# E8-F.net
KiCad netlist of a schematic drawn in EAGLE
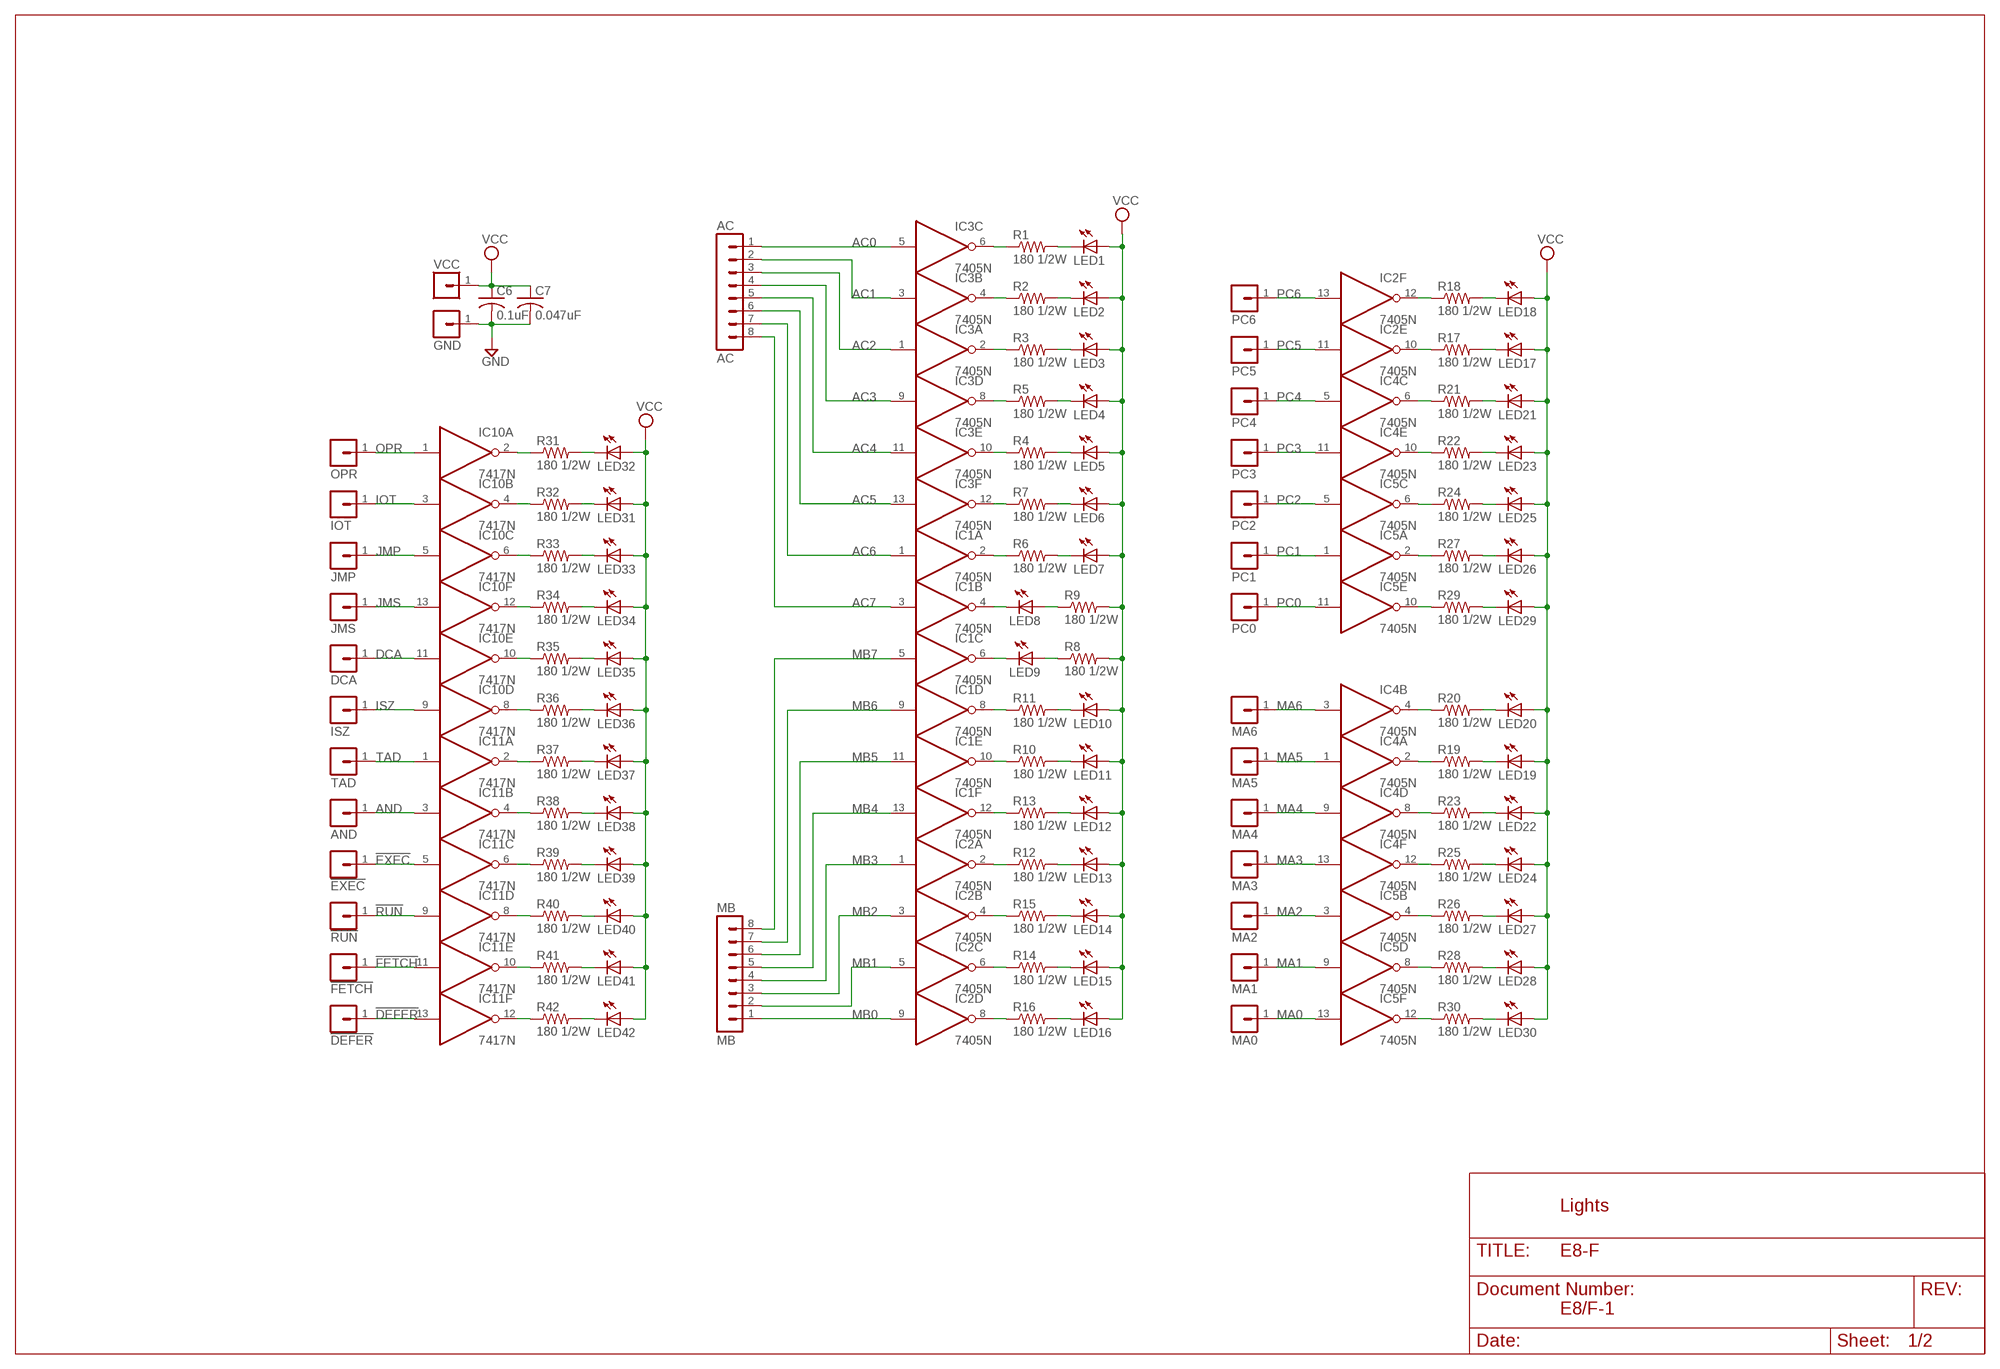
[diagram p0: schematic, sheet 1]
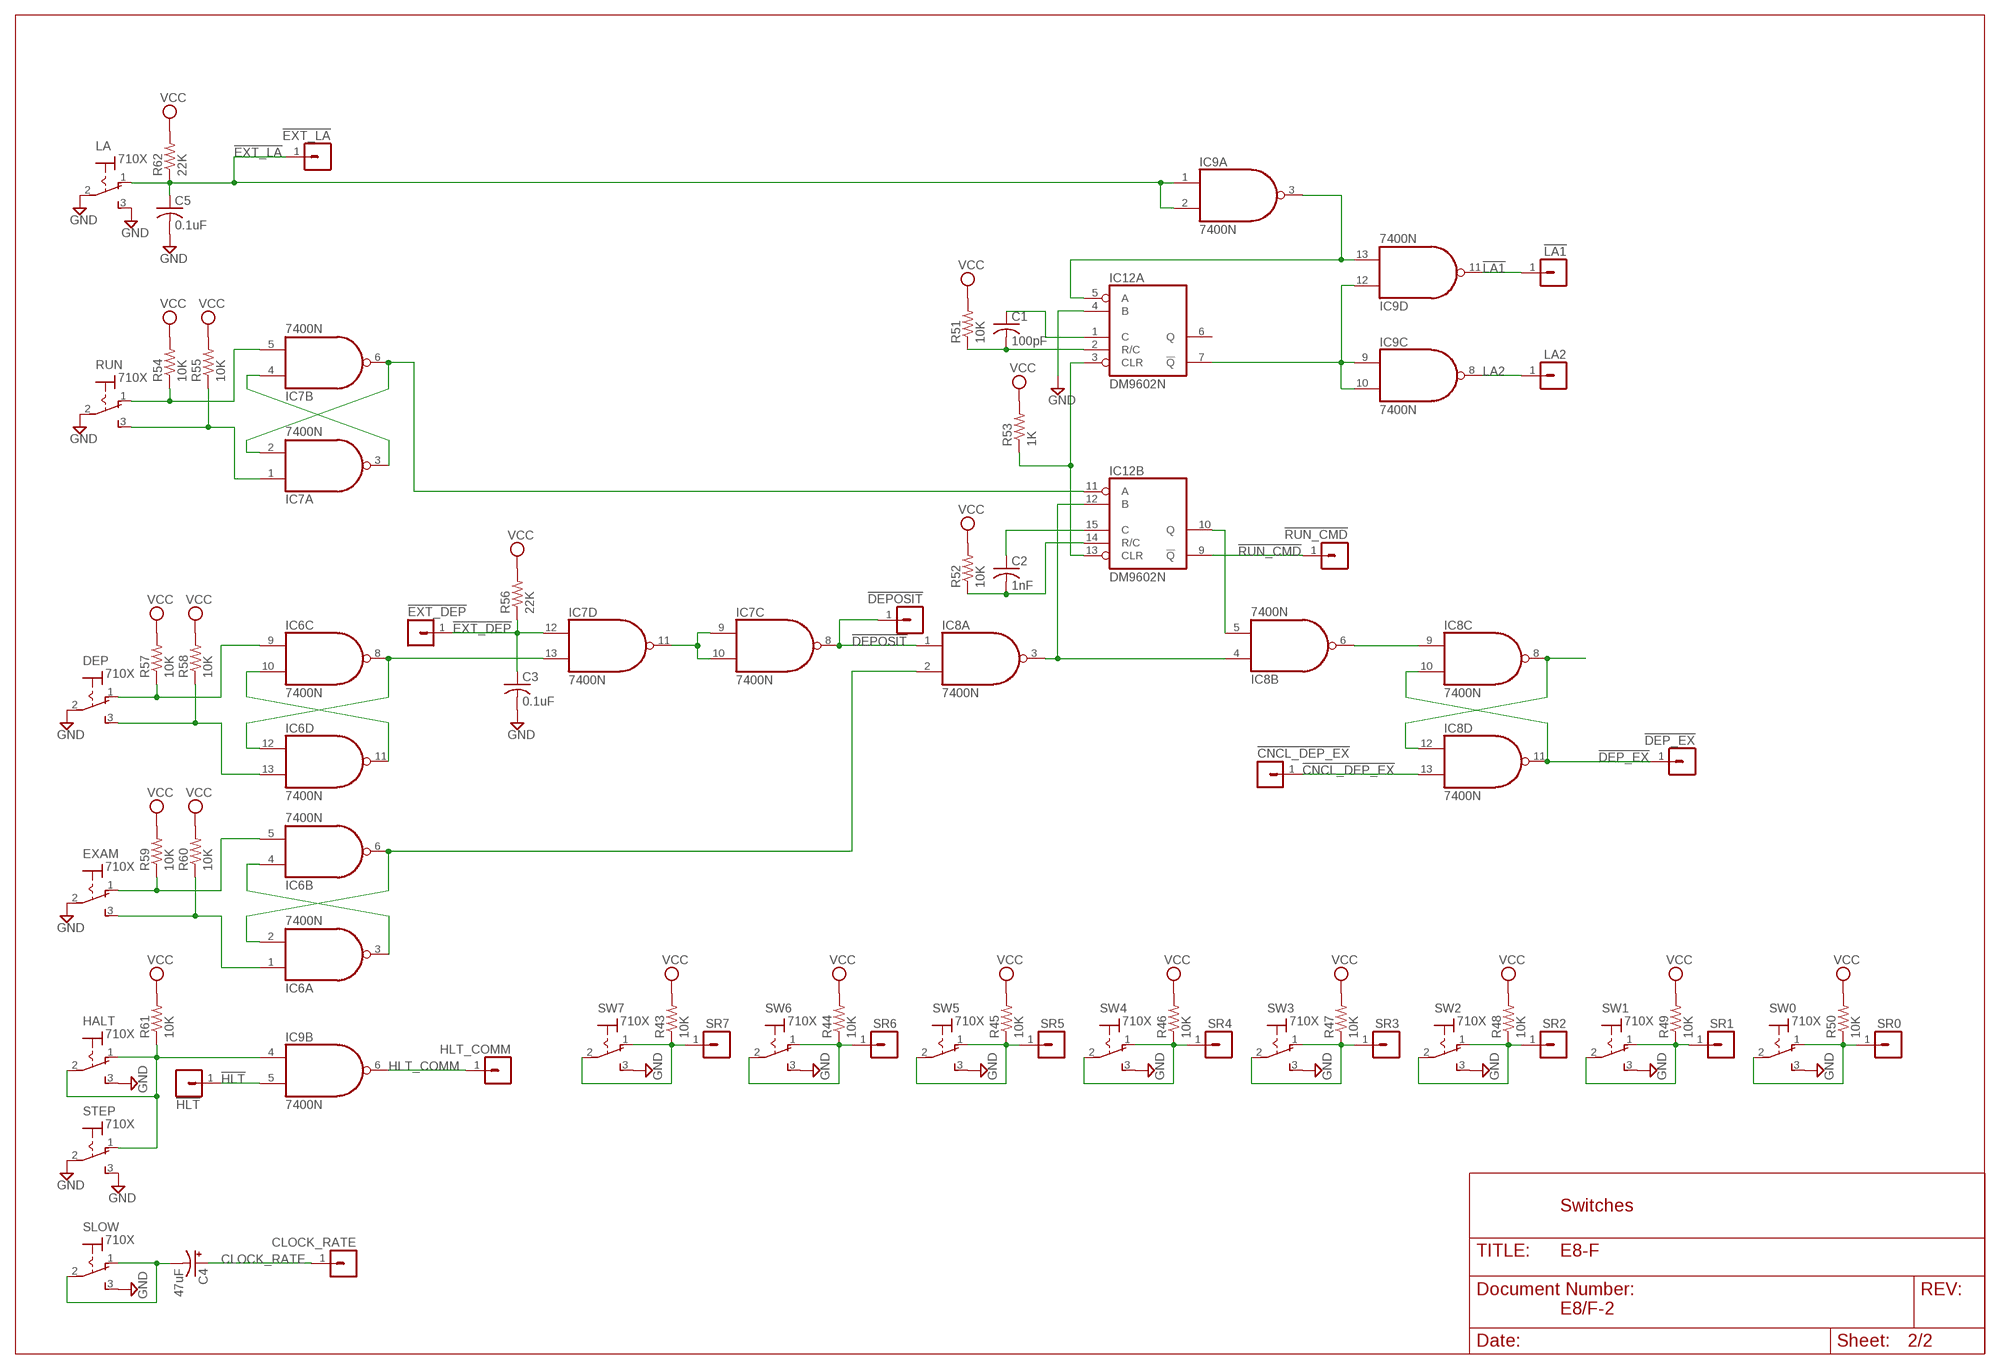
[diagram p1: schematic, sheet 2]

(export (version "E")
  (design (tool "Eeschema 10.0.6"))
  (components
    (comp (ref "!DEFER")
      (value "MA01-1")
      (footprint "eagle-import:MA01-1")
      (libsource (lib "eagle-import") (part "MA01-1"))
    )
    (comp (ref "!EXEC")
      (value "MA01-1")
      (footprint "eagle-import:MA01-1")
      (libsource (lib "eagle-import") (part "MA01-1"))
    )
    (comp (ref "!FETCH")
      (value "MA01-1")
      (footprint "eagle-import:MA01-1")
      (libsource (lib "eagle-import") (part "MA01-1"))
    )
    (comp (ref "!RUN")
      (value "MA01-1")
      (footprint "eagle-import:MA01-1")
      (libsource (lib "eagle-import") (part "MA01-1"))
    )
    (comp (ref "AC")
      (value "AC")
      (footprint "eagle-import:MA08-1")
      (libsource (lib "eagle-import") (part "MA08-1"))
    )
    (comp (ref "AND")
      (value "MA01-1")
      (footprint "eagle-import:MA01-1")
      (libsource (lib "eagle-import") (part "MA01-1"))
    )
    (comp (ref "C6")
      (value "0.1uF")
      (footprint "eagle-import:C075-032X103")
      (libsource (lib "eagle-import") (part "C-US075-032X103"))
    )
    (comp (ref "C7")
      (value "0.047uF")
      (footprint "eagle-import:C075-032X103")
      (libsource (lib "eagle-import") (part "C-US075-032X103"))
    )
    (comp (ref "DCA")
      (value "MA01-1")
      (footprint "eagle-import:MA01-1")
      (libsource (lib "eagle-import") (part "MA01-1"))
    )
    (comp (ref "GND")
      (value "MA01-1")
      (footprint "eagle-import:MA01-1")
      (libsource (lib "eagle-import") (part "MA01-1"))
    )
    (comp (ref "IC1")
      (value "7405N")
      (footprint "eagle-import:DIL14")
      (libsource (lib "eagle-import") (part "7405N"))
    )
    (comp (ref "IC2")
      (value "7405N")
      (footprint "eagle-import:DIL14")
      (libsource (lib "eagle-import") (part "7405N"))
    )
    (comp (ref "IC3")
      (value "7405N")
      (footprint "eagle-import:DIL14")
      (libsource (lib "eagle-import") (part "7405N"))
    )
    (comp (ref "IC4")
      (value "7405N")
      (footprint "eagle-import:DIL14")
      (libsource (lib "eagle-import") (part "7405N"))
    )
    (comp (ref "IC5")
      (value "7405N")
      (footprint "eagle-import:DIL14")
      (libsource (lib "eagle-import") (part "7405N"))
    )
    (comp (ref "IC10")
      (value "7417N")
      (footprint "eagle-import:DIL14")
      (libsource (lib "eagle-import") (part "7417N"))
    )
    (comp (ref "IC11")
      (value "7417N")
      (footprint "eagle-import:DIL14")
      (libsource (lib "eagle-import") (part "7417N"))
    )
    (comp (ref "IOT")
      (value "MA01-1")
      (footprint "eagle-import:MA01-1")
      (libsource (lib "eagle-import") (part "MA01-1"))
    )
    (comp (ref "ISZ")
      (value "MA01-1")
      (footprint "eagle-import:MA01-1")
      (libsource (lib "eagle-import") (part "MA01-1"))
    )
    (comp (ref "JMP")
      (value "MA01-1")
      (footprint "eagle-import:MA01-1")
      (libsource (lib "eagle-import") (part "MA01-1"))
    )
    (comp (ref "JMS")
      (value "MA01-1")
      (footprint "eagle-import:MA01-1")
      (libsource (lib "eagle-import") (part "MA01-1"))
    )
    (comp (ref "LED1")
      (value "LED5MM")
      (footprint "eagle-import:LED5MM")
      (libsource (lib "eagle-import") (part "LED5MM"))
    )
    (comp (ref "LED2")
      (value "LED5MM")
      (footprint "eagle-import:LED5MM")
      (libsource (lib "eagle-import") (part "LED5MM"))
    )
    (comp (ref "LED3")
      (value "LED5MM")
      (footprint "eagle-import:LED5MM")
      (libsource (lib "eagle-import") (part "LED5MM"))
    )
    (comp (ref "LED4")
      (value "LED5MM")
      (footprint "eagle-import:LED5MM")
      (libsource (lib "eagle-import") (part "LED5MM"))
    )
    (comp (ref "LED5")
      (value "LED5MM")
      (footprint "eagle-import:LED5MM")
      (libsource (lib "eagle-import") (part "LED5MM"))
    )
    (comp (ref "LED6")
      (value "LED5MM")
      (footprint "eagle-import:LED5MM")
      (libsource (lib "eagle-import") (part "LED5MM"))
    )
    (comp (ref "LED7")
      (value "LED5MM")
      (footprint "eagle-import:LED5MM")
      (libsource (lib "eagle-import") (part "LED5MM"))
    )
    (comp (ref "LED8")
      (value "LED5MM")
      (footprint "eagle-import:LED5MM")
      (libsource (lib "eagle-import") (part "LED5MM"))
    )
    (comp (ref "LED9")
      (value "LED5MM")
      (footprint "eagle-import:LED5MM")
      (libsource (lib "eagle-import") (part "LED5MM"))
    )
    (comp (ref "LED10")
      (value "LED5MM")
      (footprint "eagle-import:LED5MM")
      (libsource (lib "eagle-import") (part "LED5MM"))
    )
    (comp (ref "LED11")
      (value "LED5MM")
      (footprint "eagle-import:LED5MM")
      (libsource (lib "eagle-import") (part "LED5MM"))
    )
    (comp (ref "LED12")
      (value "LED5MM")
      (footprint "eagle-import:LED5MM")
      (libsource (lib "eagle-import") (part "LED5MM"))
    )
    (comp (ref "LED13")
      (value "LED5MM")
      (footprint "eagle-import:LED5MM")
      (libsource (lib "eagle-import") (part "LED5MM"))
    )
    (comp (ref "LED14")
      (value "LED5MM")
      (footprint "eagle-import:LED5MM")
      (libsource (lib "eagle-import") (part "LED5MM"))
    )
    (comp (ref "LED15")
      (value "LED5MM")
      (footprint "eagle-import:LED5MM")
      (libsource (lib "eagle-import") (part "LED5MM"))
    )
    (comp (ref "LED16")
      (value "LED5MM")
      (footprint "eagle-import:LED5MM")
      (libsource (lib "eagle-import") (part "LED5MM"))
    )
    (comp (ref "LED17")
      (value "LED5MM")
      (footprint "eagle-import:LED5MM")
      (libsource (lib "eagle-import") (part "LED5MM"))
    )
    (comp (ref "LED18")
      (value "LED5MM")
      (footprint "eagle-import:LED5MM")
      (libsource (lib "eagle-import") (part "LED5MM"))
    )
    (comp (ref "LED19")
      (value "LED5MM")
      (footprint "eagle-import:LED5MM")
      (libsource (lib "eagle-import") (part "LED5MM"))
    )
    (comp (ref "LED20")
      (value "LED5MM")
      (footprint "eagle-import:LED5MM")
      (libsource (lib "eagle-import") (part "LED5MM"))
    )
    (comp (ref "LED21")
      (value "LED5MM")
      (footprint "eagle-import:LED5MM")
      (libsource (lib "eagle-import") (part "LED5MM"))
    )
    (comp (ref "LED22")
      (value "LED5MM")
      (footprint "eagle-import:LED5MM")
      (libsource (lib "eagle-import") (part "LED5MM"))
    )
    (comp (ref "LED23")
      (value "LED5MM")
      (footprint "eagle-import:LED5MM")
      (libsource (lib "eagle-import") (part "LED5MM"))
    )
    (comp (ref "LED24")
      (value "LED5MM")
      (footprint "eagle-import:LED5MM")
      (libsource (lib "eagle-import") (part "LED5MM"))
    )
    (comp (ref "LED25")
      (value "LED5MM")
      (footprint "eagle-import:LED5MM")
      (libsource (lib "eagle-import") (part "LED5MM"))
    )
    (comp (ref "LED26")
      (value "LED5MM")
      (footprint "eagle-import:LED5MM")
      (libsource (lib "eagle-import") (part "LED5MM"))
    )
    (comp (ref "LED27")
      (value "LED5MM")
      (footprint "eagle-import:LED5MM")
      (libsource (lib "eagle-import") (part "LED5MM"))
    )
    (comp (ref "LED28")
      (value "LED5MM")
      (footprint "eagle-import:LED5MM")
      (libsource (lib "eagle-import") (part "LED5MM"))
    )
    (comp (ref "LED29")
      (value "LED5MM")
      (footprint "eagle-import:LED5MM")
      (libsource (lib "eagle-import") (part "LED5MM"))
    )
    (comp (ref "LED30")
      (value "LED5MM")
      (footprint "eagle-import:LED5MM")
      (libsource (lib "eagle-import") (part "LED5MM"))
    )
    (comp (ref "LED31")
      (value "LED5MM")
      (footprint "eagle-import:LED5MM")
      (libsource (lib "eagle-import") (part "LED5MM"))
    )
    (comp (ref "LED32")
      (value "LED5MM")
      (footprint "eagle-import:LED5MM")
      (libsource (lib "eagle-import") (part "LED5MM"))
    )
    (comp (ref "LED33")
      (value "LED5MM")
      (footprint "eagle-import:LED5MM")
      (libsource (lib "eagle-import") (part "LED5MM"))
    )
    (comp (ref "LED34")
      (value "LED5MM")
      (footprint "eagle-import:LED5MM")
      (libsource (lib "eagle-import") (part "LED5MM"))
    )
    (comp (ref "LED35")
      (value "LED5MM")
      (footprint "eagle-import:LED5MM")
      (libsource (lib "eagle-import") (part "LED5MM"))
    )
    (comp (ref "LED36")
      (value "LED5MM")
      (footprint "eagle-import:LED5MM")
      (libsource (lib "eagle-import") (part "LED5MM"))
    )
    (comp (ref "LED37")
      (value "LED5MM")
      (footprint "eagle-import:LED5MM")
      (libsource (lib "eagle-import") (part "LED5MM"))
    )
    (comp (ref "LED38")
      (value "LED5MM")
      (footprint "eagle-import:LED5MM")
      (libsource (lib "eagle-import") (part "LED5MM"))
    )
    (comp (ref "LED39")
      (value "LED5MM")
      (footprint "eagle-import:LED5MM")
      (libsource (lib "eagle-import") (part "LED5MM"))
    )
    (comp (ref "LED40")
      (value "LED5MM")
      (footprint "eagle-import:LED5MM")
      (libsource (lib "eagle-import") (part "LED5MM"))
    )
    (comp (ref "LED41")
      (value "LED5MM")
      (footprint "eagle-import:LED5MM")
      (libsource (lib "eagle-import") (part "LED5MM"))
    )
    (comp (ref "LED42")
      (value "LED5MM")
      (footprint "eagle-import:LED5MM")
      (libsource (lib "eagle-import") (part "LED5MM"))
    )
    (comp (ref "MA0")
      (value "MA01-1")
      (footprint "eagle-import:MA01-1")
      (libsource (lib "eagle-import") (part "MA01-1"))
    )
    (comp (ref "MA1")
      (value "MA01-1")
      (footprint "eagle-import:MA01-1")
      (libsource (lib "eagle-import") (part "MA01-1"))
    )
    (comp (ref "MA2")
      (value "MA01-1")
      (footprint "eagle-import:MA01-1")
      (libsource (lib "eagle-import") (part "MA01-1"))
    )
    (comp (ref "MA3")
      (value "MA01-1")
      (footprint "eagle-import:MA01-1")
      (libsource (lib "eagle-import") (part "MA01-1"))
    )
    (comp (ref "MA4")
      (value "MA01-1")
      (footprint "eagle-import:MA01-1")
      (libsource (lib "eagle-import") (part "MA01-1"))
    )
    (comp (ref "MA5")
      (value "MA01-1")
      (footprint "eagle-import:MA01-1")
      (libsource (lib "eagle-import") (part "MA01-1"))
    )
    (comp (ref "MA6")
      (value "MA01-1")
      (footprint "eagle-import:MA01-1")
      (libsource (lib "eagle-import") (part "MA01-1"))
    )
    (comp (ref "MB")
      (value "MB")
      (footprint "eagle-import:MA08-1")
      (libsource (lib "eagle-import") (part "MA08-1"))
    )
    (comp (ref "OPR")
      (value "MA01-1")
      (footprint "eagle-import:MA01-1")
      (libsource (lib "eagle-import") (part "MA01-1"))
    )
    (comp (ref "PC0")
      (value "MA01-1")
      (footprint "eagle-import:MA01-1")
      (libsource (lib "eagle-import") (part "MA01-1"))
    )
    (comp (ref "PC1")
      (value "MA01-1")
      (footprint "eagle-import:MA01-1")
      (libsource (lib "eagle-import") (part "MA01-1"))
    )
    (comp (ref "PC2")
      (value "MA01-1")
      (footprint "eagle-import:MA01-1")
      (libsource (lib "eagle-import") (part "MA01-1"))
    )
    (comp (ref "PC3")
      (value "MA01-1")
      (footprint "eagle-import:MA01-1")
      (libsource (lib "eagle-import") (part "MA01-1"))
    )
    (comp (ref "PC4")
      (value "MA01-1")
      (footprint "eagle-import:MA01-1")
      (libsource (lib "eagle-import") (part "MA01-1"))
    )
    (comp (ref "PC5")
      (value "MA01-1")
      (footprint "eagle-import:MA01-1")
      (libsource (lib "eagle-import") (part "MA01-1"))
    )
    (comp (ref "PC6")
      (value "MA01-1")
      (footprint "eagle-import:MA01-1")
      (libsource (lib "eagle-import") (part "MA01-1"))
    )
    (comp (ref "R1")
      (value "180 1/2W")
      (footprint "eagle-import:0309_.45")
      (libsource (lib "eagle-import") (part "R-US_0309/.45"))
    )
    (comp (ref "R2")
      (value "180 1/2W")
      (footprint "eagle-import:0309_.45")
      (libsource (lib "eagle-import") (part "R-US_0309/.45"))
    )
    (comp (ref "R3")
      (value "180 1/2W")
      (footprint "eagle-import:0309_.45")
      (libsource (lib "eagle-import") (part "R-US_0309/.45"))
    )
    (comp (ref "R4")
      (value "180 1/2W")
      (footprint "eagle-import:0309_12")
      (libsource (lib "eagle-import") (part "rcl_R-US_0309/12"))
    )
    (comp (ref "R5")
      (value "180 1/2W")
      (footprint "eagle-import:0309_.45")
      (libsource (lib "eagle-import") (part "R-US_0309/.45"))
    )
    (comp (ref "R6")
      (value "180 1/2W")
      (footprint "eagle-import:0309_12")
      (libsource (lib "eagle-import") (part "rcl_R-US_0309/12"))
    )
    (comp (ref "R7")
      (value "180 1/2W")
      (footprint "eagle-import:0309_.45")
      (libsource (lib "eagle-import") (part "R-US_0309/.45"))
    )
    (comp (ref "R8")
      (value "180 1/2W")
      (footprint "eagle-import:0309_12")
      (libsource (lib "eagle-import") (part "rcl_R-US_0309/12"))
    )
    (comp (ref "R9")
      (value "180 1/2W")
      (footprint "eagle-import:0309_12")
      (libsource (lib "eagle-import") (part "rcl_R-US_0309/12"))
    )
    (comp (ref "R10")
      (value "180 1/2W")
      (footprint "eagle-import:0309_.45")
      (libsource (lib "eagle-import") (part "R-US_0309/.45"))
    )
    (comp (ref "R11")
      (value "180 1/2W")
      (footprint "eagle-import:0309_11")
      (libsource (lib "eagle-import") (part "R-US_0309/11"))
    )
    (comp (ref "R12")
      (value "180 1/2W")
      (footprint "eagle-import:0309_12")
      (libsource (lib "eagle-import") (part "rcl_R-US_0309/12"))
    )
    (comp (ref "R13")
      (value "180 1/2W")
      (footprint "eagle-import:0309_.45")
      (libsource (lib "eagle-import") (part "R-US_0309/.45"))
    )
    (comp (ref "R14")
      (value "180 1/2W")
      (footprint "eagle-import:0309_.45")
      (libsource (lib "eagle-import") (part "R-US_0309/.45"))
    )
    (comp (ref "R15")
      (value "180 1/2W")
      (footprint "eagle-import:0309_12")
      (libsource (lib "eagle-import") (part "rcl_R-US_0309/12"))
    )
    (comp (ref "R16")
      (value "180 1/2W")
      (footprint "eagle-import:0309_12")
      (libsource (lib "eagle-import") (part "rcl_R-US_0309/12"))
    )
    (comp (ref "R17")
      (value "180 1/2W")
      (footprint "eagle-import:0309_12")
      (libsource (lib "eagle-import") (part "rcl_R-US_0309/12"))
    )
    (comp (ref "R18")
      (value "180 1/2W")
      (footprint "eagle-import:0309_12")
      (libsource (lib "eagle-import") (part "rcl_R-US_0309/12"))
    )
    (comp (ref "R19")
      (value "180 1/2W")
      (footprint "eagle-import:0309_12")
      (libsource (lib "eagle-import") (part "R-US_0309/12"))
    )
    (comp (ref "R20")
      (value "180 1/2W")
      (footprint "eagle-import:0309_15")
      (libsource (lib "eagle-import") (part "R-US_0309/15"))
    )
    (comp (ref "R21")
      (value "180 1/2W")
      (footprint "eagle-import:0309_.45")
      (libsource (lib "eagle-import") (part "R-US_0309/.45"))
    )
    (comp (ref "R22")
      (value "180 1/2W")
      (footprint "eagle-import:0309_10")
      (libsource (lib "eagle-import") (part "R-US_0309/10"))
    )
    (comp (ref "R23")
      (value "180 1/2W")
      (footprint "eagle-import:0309_10")
      (libsource (lib "eagle-import") (part "rcl_R-US_0309/10"))
    )
    (comp (ref "R24")
      (value "180 1/2W")
      (footprint "eagle-import:0309_12")
      (libsource (lib "eagle-import") (part "rcl_R-US_0309/12"))
    )
    (comp (ref "R25")
      (value "180 1/2W")
      (footprint "eagle-import:0309_10")
      (libsource (lib "eagle-import") (part "rcl_R-US_0309/10"))
    )
    (comp (ref "R26")
      (value "180 1/2W")
      (footprint "eagle-import:0309_10")
      (libsource (lib "eagle-import") (part "R-US_0309/10"))
    )
    (comp (ref "R27")
      (value "180 1/2W")
      (footprint "eagle-import:0309_15")
      (libsource (lib "eagle-import") (part "R-US_0309/15"))
    )
    (comp (ref "R28")
      (value "180 1/2W")
      (footprint "eagle-import:0309_.45")
      (libsource (lib "eagle-import") (part "R-US_0309/.45"))
    )
    (comp (ref "R29")
      (value "180 1/2W")
      (footprint "eagle-import:0309_.45")
      (libsource (lib "eagle-import") (part "R-US_0309/.45"))
    )
    (comp (ref "R30")
      (value "180 1/2W")
      (footprint "eagle-import:0309_.45")
      (libsource (lib "eagle-import") (part "R-US_0309/.45"))
    )
    (comp (ref "R31")
      (value "180 1/2W")
      (footprint "eagle-import:0309_8")
      (libsource (lib "eagle-import") (part "R-US_0309/8"))
    )
    (comp (ref "R32")
      (value "180 1/2W")
      (footprint "eagle-import:0309_8")
      (libsource (lib "eagle-import") (part "R-US_0309/8"))
    )
    (comp (ref "R33")
      (value "180 1/2W")
      (footprint "eagle-import:0309_8")
      (libsource (lib "eagle-import") (part "R-US_0309/8"))
    )
    (comp (ref "R34")
      (value "180 1/2W")
      (footprint "eagle-import:0309_8")
      (libsource (lib "eagle-import") (part "R-US_0309/8"))
    )
    (comp (ref "R35")
      (value "180 1/2W")
      (footprint "eagle-import:0309_8")
      (libsource (lib "eagle-import") (part "R-US_0309/8"))
    )
    (comp (ref "R36")
      (value "180 1/2W")
      (footprint "eagle-import:0309_8")
      (libsource (lib "eagle-import") (part "R-US_0309/8"))
    )
    (comp (ref "R37")
      (value "180 1/2W")
      (footprint "eagle-import:0309_8")
      (libsource (lib "eagle-import") (part "R-US_0309/8"))
    )
    (comp (ref "R38")
      (value "180 1/2W")
      (footprint "eagle-import:0309_8")
      (libsource (lib "eagle-import") (part "R-US_0309/8"))
    )
    (comp (ref "R39")
      (value "180 1/2W")
      (footprint "eagle-import:0309_10")
      (libsource (lib "eagle-import") (part "R-US_0309/10"))
    )
    (comp (ref "R40")
      (value "180 1/2W")
      (footprint "eagle-import:0309_10")
      (libsource (lib "eagle-import") (part "R-US_0309/10"))
    )
    (comp (ref "R41")
      (value "180 1/2W")
      (footprint "eagle-import:0309_10")
      (libsource (lib "eagle-import") (part "R-US_0309/10"))
    )
    (comp (ref "R42")
      (value "180 1/2W")
      (footprint "eagle-import:0309_10")
      (libsource (lib "eagle-import") (part "R-US_0309/10"))
    )
    (comp (ref "TAD")
      (value "MA01-1")
      (footprint "eagle-import:MA01-1")
      (libsource (lib "eagle-import") (part "MA01-1"))
    )
    (comp (ref "VCC")
      (value "MA01-1")
      (footprint "eagle-import:MA01-1")
      (libsource (lib "eagle-import") (part "MA01-1"))
    )
    (comp (ref "!CNCL_DEP_EX")
      (value "MA01-1")
      (footprint "eagle-import:MA01-1")
      (libsource (lib "eagle-import") (part "MA01-1"))
    )
    (comp (ref "!DEPOSIT")
      (value "MA01-1")
      (footprint "eagle-import:MA01-1")
      (libsource (lib "eagle-import") (part "MA01-1"))
    )
    (comp (ref "!DEP_EX")
      (value "MA01-1")
      (footprint "eagle-import:MA01-1")
      (libsource (lib "eagle-import") (part "MA01-1"))
    )
    (comp (ref "!EXT_DEP")
      (value "MA01-1")
      (footprint "eagle-import:MA01-1")
      (libsource (lib "eagle-import") (part "MA01-1"))
    )
    (comp (ref "!EXT_LA")
      (value "MA01-1")
      (footprint "eagle-import:MA01-1")
      (libsource (lib "eagle-import") (part "MA01-1"))
    )
    (comp (ref "!HLT")
      (value "MA01-1")
      (footprint "eagle-import:MA01-1")
      (libsource (lib "eagle-import") (part "MA01-1"))
    )
    (comp (ref "!LA1")
      (value "MA01-1")
      (footprint "eagle-import:MA01-1")
      (libsource (lib "eagle-import") (part "MA01-1"))
    )
    (comp (ref "!RUN_CMD")
      (value "MA01-1")
      (footprint "eagle-import:MA01-1")
      (libsource (lib "eagle-import") (part "MA01-1"))
    )
    (comp (ref "C1")
      (value "100pF")
      (footprint "eagle-import:C075-032X103")
      (libsource (lib "eagle-import") (part "C-US075-032X103"))
    )
    (comp (ref "C2")
      (value "1nF")
      (footprint "eagle-import:C075-032X103")
      (libsource (lib "eagle-import") (part "C-US075-032X103"))
    )
    (comp (ref "C3")
      (value "0.1uF")
      (footprint "eagle-import:C063-025X075")
      (libsource (lib "eagle-import") (part "C-US"))
    )
    (comp (ref "C4")
      (value "47uF")
      (footprint "eagle-import:B45181C")
      (libsource (lib "eagle-import") (part "CPOL-USB45181C"))
    )
    (comp (ref "C5")
      (value "0.1uF")
      (footprint "eagle-import:C075-032X103")
      (libsource (lib "eagle-import") (part "C-US075-032X103"))
    )
    (comp (ref "CLOCK_RATE")
      (value "MA01-1")
      (footprint "eagle-import:MA01-1")
      (libsource (lib "eagle-import") (part "MA01-1"))
    )
    (comp (ref "DEP")
      (value "710X")
      (footprint "eagle-import:7109")
      (libsource (lib "eagle-import") (part "710X"))
    )
    (comp (ref "EXAM")
      (value "710X")
      (footprint "eagle-import:7109")
      (libsource (lib "eagle-import") (part "710X"))
    )
    (comp (ref "HALT")
      (value "710X")
      (footprint "eagle-import:7109")
      (libsource (lib "eagle-import") (part "710X"))
    )
    (comp (ref "HLT_COMM")
      (value "MA01-1")
      (footprint "eagle-import:MA01-1")
      (libsource (lib "eagle-import") (part "MA01-1"))
    )
    (comp (ref "IC6")
      (value "7400N")
      (footprint "eagle-import:DIL14")
      (libsource (lib "eagle-import") (part "7400N"))
    )
    (comp (ref "IC7")
      (value "7400N")
      (footprint "eagle-import:DIL14")
      (libsource (lib "eagle-import") (part "7400N"))
    )
    (comp (ref "IC8")
      (value "7400N")
      (footprint "eagle-import:DIL14")
      (libsource (lib "eagle-import") (part "7400N"))
    )
    (comp (ref "IC9")
      (value "7400N")
      (footprint "eagle-import:DIL14")
      (libsource (lib "eagle-import") (part "7400N"))
    )
    (comp (ref "IC12")
      (value "DM9602N")
      (footprint "eagle-import:DIL16")
      (libsource (lib "eagle-import") (part "DM9602N"))
    )
    (comp (ref "LA")
      (value "710X")
      (footprint "eagle-import:7109")
      (libsource (lib "eagle-import") (part "710X"))
    )
    (comp (ref "LA2")
      (value "MA01-1")
      (footprint "eagle-import:MA01-1")
      (libsource (lib "eagle-import") (part "MA01-1"))
    )
    (comp (ref "R43")
      (value "10K")
      (footprint "eagle-import:0207_12")
      (libsource (lib "eagle-import") (part "rcl_R-US_0207/12"))
    )
    (comp (ref "R44")
      (value "10K")
      (footprint "eagle-import:0207_12")
      (libsource (lib "eagle-import") (part "rcl_R-US_0207/12"))
    )
    (comp (ref "R45")
      (value "10K")
      (footprint "eagle-import:0207_12")
      (libsource (lib "eagle-import") (part "rcl_R-US_0207/12"))
    )
    (comp (ref "R46")
      (value "10K")
      (footprint "eagle-import:0207_12")
      (libsource (lib "eagle-import") (part "rcl_R-US_0207/12"))
    )
    (comp (ref "R47")
      (value "10K")
      (footprint "eagle-import:0207_12")
      (libsource (lib "eagle-import") (part "rcl_R-US_0207/12"))
    )
    (comp (ref "R48")
      (value "10K")
      (footprint "eagle-import:0207_12")
      (libsource (lib "eagle-import") (part "rcl_R-US_0207/12"))
    )
    (comp (ref "R49")
      (value "10K")
      (footprint "eagle-import:0207_12")
      (libsource (lib "eagle-import") (part "rcl_R-US_0207/12"))
    )
    (comp (ref "R50")
      (value "10K")
      (footprint "eagle-import:0207_12")
      (libsource (lib "eagle-import") (part "rcl_R-US_0207/12"))
    )
    (comp (ref "R51")
      (value "10K")
      (footprint "eagle-import:0207_10")
      (libsource (lib "eagle-import") (part "rcl_R-US_0207/10"))
    )
    (comp (ref "R52")
      (value "10K")
      (footprint "eagle-import:0207_15")
      (libsource (lib "eagle-import") (part "rcl_R-US_0207/15"))
    )
    (comp (ref "R53")
      (value "1K")
      (footprint "eagle-import:0204_6")
      (libsource (lib "eagle-import") (part "R-US_0204/6"))
    )
    (comp (ref "R54")
      (value "10K")
      (footprint "eagle-import:0207_13")
      (libsource (lib "eagle-import") (part "R-US_0207/13"))
    )
    (comp (ref "R55")
      (value "10K")
      (footprint "eagle-import:0207_13")
      (libsource (lib "eagle-import") (part "R-US_0207/13"))
    )
    (comp (ref "R56")
      (value "22K")
      (footprint "eagle-import:0207_10")
      (libsource (lib "eagle-import") (part "R-US_0207/10"))
    )
    (comp (ref "R57")
      (value "10K")
      (footprint "eagle-import:0207_13")
      (libsource (lib "eagle-import") (part "R-US_0207/13"))
    )
    (comp (ref "R58")
      (value "10K")
      (footprint "eagle-import:0207_13")
      (libsource (lib "eagle-import") (part "R-US_0207/13"))
    )
    (comp (ref "R59")
      (value "10K")
      (footprint "eagle-import:0207_13")
      (libsource (lib "eagle-import") (part "R-US_0207/13"))
    )
    (comp (ref "R60")
      (value "10K")
      (footprint "eagle-import:0207_13")
      (libsource (lib "eagle-import") (part "R-US_0207/13"))
    )
    (comp (ref "R61")
      (value "10K")
      (footprint "eagle-import:0207_22")
      (libsource (lib "eagle-import") (part "R-US_0207/22"))
    )
    (comp (ref "R62")
      (value "22K")
      (footprint "eagle-import:0207_13")
      (libsource (lib "eagle-import") (part "R-US_0207/13"))
    )
    (comp (ref "RUN")
      (value "710X")
      (footprint "eagle-import:7109")
      (libsource (lib "eagle-import") (part "710X"))
    )
    (comp (ref "SLOW")
      (value "710X")
      (footprint "eagle-import:7109")
      (libsource (lib "eagle-import") (part "710X"))
    )
    (comp (ref "SR0")
      (value "MA01-1")
      (footprint "eagle-import:MA01-1")
      (libsource (lib "eagle-import") (part "MA01-1"))
    )
    (comp (ref "SR1")
      (value "MA01-1")
      (footprint "eagle-import:MA01-1")
      (libsource (lib "eagle-import") (part "MA01-1"))
    )
    (comp (ref "SR2")
      (value "MA01-1")
      (footprint "eagle-import:MA01-1")
      (libsource (lib "eagle-import") (part "MA01-1"))
    )
    (comp (ref "SR3")
      (value "MA01-1")
      (footprint "eagle-import:MA01-1")
      (libsource (lib "eagle-import") (part "MA01-1"))
    )
    (comp (ref "SR4")
      (value "MA01-1")
      (footprint "eagle-import:MA01-1")
      (libsource (lib "eagle-import") (part "MA01-1"))
    )
    (comp (ref "SR5")
      (value "MA01-1")
      (footprint "eagle-import:MA01-1")
      (libsource (lib "eagle-import") (part "MA01-1"))
    )
    (comp (ref "SR6")
      (value "MA01-1")
      (footprint "eagle-import:MA01-1")
      (libsource (lib "eagle-import") (part "MA01-1"))
    )
    (comp (ref "SR7")
      (value "MA01-1")
      (footprint "eagle-import:MA01-1")
      (libsource (lib "eagle-import") (part "MA01-1"))
    )
    (comp (ref "STEP")
      (value "710X")
      (footprint "eagle-import:7109")
      (libsource (lib "eagle-import") (part "710X"))
    )
    (comp (ref "SW0")
      (value "710X")
      (footprint "eagle-import:7109")
      (libsource (lib "eagle-import") (part "710X"))
    )
    (comp (ref "SW1")
      (value "710X")
      (footprint "eagle-import:7109")
      (libsource (lib "eagle-import") (part "710X"))
    )
    (comp (ref "SW2")
      (value "710X")
      (footprint "eagle-import:7109")
      (libsource (lib "eagle-import") (part "710X"))
    )
    (comp (ref "SW3")
      (value "710X")
      (footprint "eagle-import:7109")
      (libsource (lib "eagle-import") (part "710X"))
    )
    (comp (ref "SW4")
      (value "710X")
      (footprint "eagle-import:7109")
      (libsource (lib "eagle-import") (part "710X"))
    )
    (comp (ref "SW5")
      (value "710X")
      (footprint "eagle-import:7109")
      (libsource (lib "eagle-import") (part "710X"))
    )
    (comp (ref "SW6")
      (value "710X")
      (footprint "eagle-import:7109")
      (libsource (lib "eagle-import") (part "710X"))
    )
    (comp (ref "SW7")
      (value "710X")
      (footprint "eagle-import:7109")
      (libsource (lib "eagle-import") (part "710X"))
    )
  )
  (nets
    (net (code "1") (name "AC0") (class "Default")
      (node (ref "AC") (pin "1") (pinfunction "1_1") (pintype "passive"))
      (node (ref "IC3") (pin "5") (pinfunction "I_5") (pintype "input"))
    )
    (net (code "2") (name "AC1") (class "Default")
      (node (ref "AC") (pin "2") (pinfunction "2_2") (pintype "passive"))
      (node (ref "IC3") (pin "3") (pinfunction "I_3") (pintype "input"))
    )
    (net (code "3") (name "AC2") (class "Default")
      (node (ref "AC") (pin "3") (pinfunction "3_3") (pintype "passive"))
      (node (ref "IC3") (pin "1") (pinfunction "I_1") (pintype "input"))
    )
    (net (code "4") (name "AC3") (class "Default")
      (node (ref "AC") (pin "4") (pinfunction "4_4") (pintype "passive"))
      (node (ref "IC3") (pin "9") (pinfunction "I_9") (pintype "input"))
    )
    (net (code "5") (name "AC4") (class "Default")
      (node (ref "AC") (pin "5") (pinfunction "5_5") (pintype "passive"))
      (node (ref "IC3") (pin "11") (pinfunction "I_11") (pintype "input"))
    )
    (net (code "6") (name "AC5") (class "Default")
      (node (ref "AC") (pin "6") (pinfunction "6_6") (pintype "passive"))
      (node (ref "IC3") (pin "13") (pinfunction "I_13") (pintype "input"))
    )
    (net (code "7") (name "AC6") (class "Default")
      (node (ref "AC") (pin "7") (pinfunction "7_7") (pintype "passive"))
      (node (ref "IC1") (pin "1") (pinfunction "I_1") (pintype "input"))
    )
    (net (code "8") (name "AC7") (class "Default")
      (node (ref "AC") (pin "8") (pinfunction "8_8") (pintype "passive"))
      (node (ref "IC1") (pin "3") (pinfunction "I_3") (pintype "input"))
    )
    (net (code "9") (name "AND") (class "Default")
      (node (ref "AND") (pin "1") (pinfunction "1_1") (pintype "passive"))
      (node (ref "IC11") (pin "3") (pinfunction "I_3") (pintype "input"))
    )
    (net (code "10") (name "CLOCK_RATE") (class "Default")
      (node (ref "C4") (pin "+") (pinfunction "+_+") (pintype "passive"))
      (node (ref "CLOCK_RATE") (pin "1") (pinfunction "1_1") (pintype "passive"))
    )
    (net (code "11") (name "DCA") (class "Default")
      (node (ref "DCA") (pin "1") (pinfunction "1_1") (pintype "passive"))
      (node (ref "IC10") (pin "11") (pinfunction "I_11") (pintype "input"))
    )
    (net (code "12") (name "GND") (class "Default")
      (node (ref "C3") (pin "2") (pinfunction "2_2") (pintype "passive"))
      (node (ref "C5") (pin "2") (pinfunction "2_2") (pintype "passive"))
      (node (ref "C6") (pin "2") (pinfunction "2_2") (pintype "passive"))
      (node (ref "C7") (pin "2") (pinfunction "2_2") (pintype "passive"))
      (node (ref "DEP") (pin "2") (pinfunction "P_2") (pintype "passive"))
      (node (ref "EXAM") (pin "2") (pinfunction "P_2") (pintype "passive"))
      (node (ref "GND") (pin "1") (pinfunction "1_1") (pintype "passive"))
      (node (ref "HALT") (pin "3") (pinfunction "S_3") (pintype "passive"))
      (node (ref "IC12") (pin "4") (pinfunction "B_4") (pintype "input"))
      (node (ref "LA") (pin "2") (pinfunction "P_2") (pintype "passive"))
      (node (ref "LA") (pin "3") (pinfunction "S_3") (pintype "passive"))
      (node (ref "RUN") (pin "2") (pinfunction "P_2") (pintype "passive"))
      (node (ref "SLOW") (pin "3") (pinfunction "S_3") (pintype "passive"))
      (node (ref "STEP") (pin "2") (pinfunction "P_2") (pintype "passive"))
      (node (ref "STEP") (pin "3") (pinfunction "S_3") (pintype "passive"))
      (node (ref "SW0") (pin "3") (pinfunction "S_3") (pintype "passive"))
      (node (ref "SW1") (pin "3") (pinfunction "S_3") (pintype "passive"))
      (node (ref "SW2") (pin "3") (pinfunction "S_3") (pintype "passive"))
      (node (ref "SW3") (pin "3") (pinfunction "S_3") (pintype "passive"))
      (node (ref "SW4") (pin "3") (pinfunction "S_3") (pintype "passive"))
      (node (ref "SW5") (pin "3") (pinfunction "S_3") (pintype "passive"))
      (node (ref "SW6") (pin "3") (pinfunction "S_3") (pintype "passive"))
      (node (ref "SW7") (pin "3") (pinfunction "S_3") (pintype "passive"))
    )
    (net (code "13") (name "HLT_COMM") (class "Default")
      (node (ref "HLT_COMM") (pin "1") (pinfunction "1_1") (pintype "passive"))
      (node (ref "IC9") (pin "6") (pinfunction "O_6") (pintype "output"))
    )
    (net (code "14") (name "IOT") (class "Default")
      (node (ref "IC10") (pin "3") (pinfunction "I_3") (pintype "input"))
      (node (ref "IOT") (pin "1") (pinfunction "1_1") (pintype "passive"))
    )
    (net (code "15") (name "ISZ") (class "Default")
      (node (ref "IC10") (pin "9") (pinfunction "I_9") (pintype "input"))
      (node (ref "ISZ") (pin "1") (pinfunction "1_1") (pintype "passive"))
    )
    (net (code "16") (name "JMP") (class "Default")
      (node (ref "IC10") (pin "5") (pinfunction "I_5") (pintype "input"))
      (node (ref "JMP") (pin "1") (pinfunction "1_1") (pintype "passive"))
    )
    (net (code "17") (name "JMS") (class "Default")
      (node (ref "IC10") (pin "13") (pinfunction "I_13") (pintype "input"))
      (node (ref "JMS") (pin "1") (pinfunction "1_1") (pintype "passive"))
    )
    (net (code "18") (name "LA2") (class "Default")
      (node (ref "IC9") (pin "8") (pinfunction "O_8") (pintype "output"))
      (node (ref "LA2") (pin "1") (pinfunction "1_1") (pintype "passive"))
    )
    (net (code "19") (name "MA0") (class "Default")
      (node (ref "IC5") (pin "13") (pinfunction "I_13") (pintype "input"))
      (node (ref "MA0") (pin "1") (pinfunction "1_1") (pintype "passive"))
    )
    (net (code "20") (name "MA1") (class "Default")
      (node (ref "IC5") (pin "9") (pinfunction "I_9") (pintype "input"))
      (node (ref "MA1") (pin "1") (pinfunction "1_1") (pintype "passive"))
    )
    (net (code "21") (name "MA2") (class "Default")
      (node (ref "IC5") (pin "3") (pinfunction "I_3") (pintype "input"))
      (node (ref "MA2") (pin "1") (pinfunction "1_1") (pintype "passive"))
    )
    (net (code "22") (name "MA3") (class "Default")
      (node (ref "IC4") (pin "13") (pinfunction "I_13") (pintype "input"))
      (node (ref "MA3") (pin "1") (pinfunction "1_1") (pintype "passive"))
    )
    (net (code "23") (name "MA4") (class "Default")
      (node (ref "IC4") (pin "9") (pinfunction "I_9") (pintype "input"))
      (node (ref "MA4") (pin "1") (pinfunction "1_1") (pintype "passive"))
    )
    (net (code "24") (name "MA5") (class "Default")
      (node (ref "IC4") (pin "1") (pinfunction "I_1") (pintype "input"))
      (node (ref "MA5") (pin "1") (pinfunction "1_1") (pintype "passive"))
    )
    (net (code "25") (name "MA6") (class "Default")
      (node (ref "IC4") (pin "3") (pinfunction "I_3") (pintype "input"))
      (node (ref "MA6") (pin "1") (pinfunction "1_1") (pintype "passive"))
    )
    (net (code "26") (name "MB0") (class "Default")
      (node (ref "IC2") (pin "9") (pinfunction "I_9") (pintype "input"))
      (node (ref "MB") (pin "1") (pinfunction "1_1") (pintype "passive"))
    )
    (net (code "27") (name "MB1") (class "Default")
      (node (ref "IC2") (pin "5") (pinfunction "I_5") (pintype "input"))
      (node (ref "MB") (pin "2") (pinfunction "2_2") (pintype "passive"))
    )
    (net (code "28") (name "MB2") (class "Default")
      (node (ref "IC2") (pin "3") (pinfunction "I_3") (pintype "input"))
      (node (ref "MB") (pin "3") (pinfunction "3_3") (pintype "passive"))
    )
    (net (code "29") (name "MB3") (class "Default")
      (node (ref "IC2") (pin "1") (pinfunction "I_1") (pintype "input"))
      (node (ref "MB") (pin "4") (pinfunction "4_4") (pintype "passive"))
    )
    (net (code "30") (name "MB4") (class "Default")
      (node (ref "IC1") (pin "13") (pinfunction "I_13") (pintype "input"))
      (node (ref "MB") (pin "5") (pinfunction "5_5") (pintype "passive"))
    )
    (net (code "31") (name "MB5") (class "Default")
      (node (ref "IC1") (pin "11") (pinfunction "I_11") (pintype "input"))
      (node (ref "MB") (pin "6") (pinfunction "6_6") (pintype "passive"))
    )
    (net (code "32") (name "MB6") (class "Default")
      (node (ref "IC1") (pin "9") (pinfunction "I_9") (pintype "input"))
      (node (ref "MB") (pin "7") (pinfunction "7_7") (pintype "passive"))
    )
    (net (code "33") (name "MB7") (class "Default")
      (node (ref "IC1") (pin "5") (pinfunction "I_5") (pintype "input"))
      (node (ref "MB") (pin "8") (pinfunction "8_8") (pintype "passive"))
    )
    (net (code "34") (name "Net-(DEP-O)") (class "Default")
      (node (ref "DEP") (pin "1") (pinfunction "O_1") (pintype "passive"))
      (node (ref "IC6") (pin "9") (pinfunction "I0_9") (pintype "input"))
      (node (ref "R57") (pin "1") (pinfunction "1_1") (pintype "passive"))
    )
    (net (code "35") (name "Net-(DEP-S)") (class "Default")
      (node (ref "DEP") (pin "3") (pinfunction "S_3") (pintype "passive"))
      (node (ref "IC6") (pin "13") (pinfunction "I1_13") (pintype "input"))
      (node (ref "R58") (pin "1") (pinfunction "1_1") (pintype "passive"))
    )
    (net (code "36") (name "Net-(EXAM-O)") (class "Default")
      (node (ref "EXAM") (pin "1") (pinfunction "O_1") (pintype "passive"))
      (node (ref "IC6") (pin "5") (pinfunction "I1_5") (pintype "input"))
      (node (ref "R59") (pin "1") (pinfunction "1_1") (pintype "passive"))
    )
    (net (code "37") (name "Net-(EXAM-S)") (class "Default")
      (node (ref "EXAM") (pin "3") (pinfunction "S_3") (pintype "passive"))
      (node (ref "IC6") (pin "1") (pinfunction "I0_1") (pintype "input"))
      (node (ref "R60") (pin "1") (pinfunction "1_1") (pintype "passive"))
    )
    (net (code "38") (name "Net-(HALT-O)") (class "Default")
      (node (ref "HALT") (pin "1") (pinfunction "O_1") (pintype "passive"))
      (node (ref "HALT") (pin "2") (pinfunction "P_2") (pintype "passive"))
      (node (ref "IC9") (pin "4") (pinfunction "I0_4") (pintype "input"))
      (node (ref "R61") (pin "1") (pinfunction "1_1") (pintype "passive"))
      (node (ref "STEP") (pin "1") (pinfunction "O_1") (pintype "passive"))
    )
    (net (code "39") (name "Net-(IC1A-O)") (class "Default")
      (node (ref "IC1") (pin "2") (pinfunction "O_2") (pintype "open_collector"))
      (node (ref "R6") (pin "1") (pinfunction "1_1") (pintype "passive"))
    )
    (net (code "40") (name "Net-(IC1B-O)") (class "Default")
      (node (ref "IC1") (pin "4") (pinfunction "O_4") (pintype "open_collector"))
      (node (ref "LED8") (pin "K") (pinfunction "C_K") (pintype "passive"))
    )
    (net (code "41") (name "Net-(IC1C-O)") (class "Default")
      (node (ref "IC1") (pin "6") (pinfunction "O_6") (pintype "open_collector"))
      (node (ref "LED9") (pin "K") (pinfunction "C_K") (pintype "passive"))
    )
    (net (code "42") (name "Net-(IC1D-O)") (class "Default")
      (node (ref "IC1") (pin "8") (pinfunction "O_8") (pintype "open_collector"))
      (node (ref "R11") (pin "1") (pinfunction "1_1") (pintype "passive"))
    )
    (net (code "43") (name "Net-(IC1E-O)") (class "Default")
      (node (ref "IC1") (pin "10") (pinfunction "O_10") (pintype "open_collector"))
      (node (ref "R10") (pin "1") (pinfunction "1_1") (pintype "passive"))
    )
    (net (code "44") (name "Net-(IC1F-O)") (class "Default")
      (node (ref "IC1") (pin "12") (pinfunction "O_12") (pintype "open_collector"))
      (node (ref "R13") (pin "1") (pinfunction "1_1") (pintype "passive"))
    )
    (net (code "45") (name "Net-(IC2A-O)") (class "Default")
      (node (ref "IC2") (pin "2") (pinfunction "O_2") (pintype "open_collector"))
      (node (ref "R12") (pin "1") (pinfunction "1_1") (pintype "passive"))
    )
    (net (code "46") (name "Net-(IC2B-O)") (class "Default")
      (node (ref "IC2") (pin "4") (pinfunction "O_4") (pintype "open_collector"))
      (node (ref "R15") (pin "1") (pinfunction "1_1") (pintype "passive"))
    )
    (net (code "47") (name "Net-(IC2C-O)") (class "Default")
      (node (ref "IC2") (pin "6") (pinfunction "O_6") (pintype "open_collector"))
      (node (ref "R14") (pin "1") (pinfunction "1_1") (pintype "passive"))
    )
    (net (code "48") (name "Net-(IC2D-O)") (class "Default")
      (node (ref "IC2") (pin "8") (pinfunction "O_8") (pintype "open_collector"))
      (node (ref "R16") (pin "1") (pinfunction "1_1") (pintype "passive"))
    )
    (net (code "49") (name "Net-(IC2E-O)") (class "Default")
      (node (ref "IC2") (pin "10") (pinfunction "O_10") (pintype "open_collector"))
      (node (ref "R17") (pin "1") (pinfunction "1_1") (pintype "passive"))
    )
    (net (code "50") (name "Net-(IC2F-O)") (class "Default")
      (node (ref "IC2") (pin "12") (pinfunction "O_12") (pintype "open_collector"))
      (node (ref "R18") (pin "1") (pinfunction "1_1") (pintype "passive"))
    )
    (net (code "51") (name "Net-(IC3A-O)") (class "Default")
      (node (ref "IC3") (pin "2") (pinfunction "O_2") (pintype "open_collector"))
      (node (ref "R3") (pin "1") (pinfunction "1_1") (pintype "passive"))
    )
    (net (code "52") (name "Net-(IC3B-O)") (class "Default")
      (node (ref "IC3") (pin "4") (pinfunction "O_4") (pintype "open_collector"))
      (node (ref "R2") (pin "1") (pinfunction "1_1") (pintype "passive"))
    )
    (net (code "53") (name "Net-(IC3C-O)") (class "Default")
      (node (ref "IC3") (pin "6") (pinfunction "O_6") (pintype "open_collector"))
      (node (ref "R1") (pin "1") (pinfunction "1_1") (pintype "passive"))
    )
    (net (code "54") (name "Net-(IC3D-O)") (class "Default")
      (node (ref "IC3") (pin "8") (pinfunction "O_8") (pintype "open_collector"))
      (node (ref "R5") (pin "1") (pinfunction "1_1") (pintype "passive"))
    )
    (net (code "55") (name "Net-(IC3E-O)") (class "Default")
      (node (ref "IC3") (pin "10") (pinfunction "O_10") (pintype "open_collector"))
      (node (ref "R4") (pin "1") (pinfunction "1_1") (pintype "passive"))
    )
    (net (code "56") (name "Net-(IC3F-O)") (class "Default")
      (node (ref "IC3") (pin "12") (pinfunction "O_12") (pintype "open_collector"))
      (node (ref "R7") (pin "1") (pinfunction "1_1") (pintype "passive"))
    )
    (net (code "57") (name "Net-(IC4A-O)") (class "Default")
      (node (ref "IC4") (pin "2") (pinfunction "O_2") (pintype "open_collector"))
      (node (ref "R19") (pin "1") (pinfunction "1_1") (pintype "passive"))
    )
    (net (code "58") (name "Net-(IC4B-O)") (class "Default")
      (node (ref "IC4") (pin "4") (pinfunction "O_4") (pintype "open_collector"))
      (node (ref "R20") (pin "1") (pinfunction "1_1") (pintype "passive"))
    )
    (net (code "59") (name "Net-(IC4C-O)") (class "Default")
      (node (ref "IC4") (pin "6") (pinfunction "O_6") (pintype "open_collector"))
      (node (ref "R21") (pin "1") (pinfunction "1_1") (pintype "passive"))
    )
    (net (code "60") (name "Net-(IC4D-O)") (class "Default")
      (node (ref "IC4") (pin "8") (pinfunction "O_8") (pintype "open_collector"))
      (node (ref "R23") (pin "1") (pinfunction "1_1") (pintype "passive"))
    )
    (net (code "61") (name "Net-(IC4E-O)") (class "Default")
      (node (ref "IC4") (pin "10") (pinfunction "O_10") (pintype "open_collector"))
      (node (ref "R22") (pin "1") (pinfunction "1_1") (pintype "passive"))
    )
    (net (code "62") (name "Net-(IC4F-O)") (class "Default")
      (node (ref "IC4") (pin "12") (pinfunction "O_12") (pintype "open_collector"))
      (node (ref "R25") (pin "1") (pinfunction "1_1") (pintype "passive"))
    )
    (net (code "63") (name "Net-(IC5A-O)") (class "Default")
      (node (ref "IC5") (pin "2") (pinfunction "O_2") (pintype "open_collector"))
      (node (ref "R27") (pin "1") (pinfunction "1_1") (pintype "passive"))
    )
    (net (code "64") (name "Net-(IC5B-O)") (class "Default")
      (node (ref "IC5") (pin "4") (pinfunction "O_4") (pintype "open_collector"))
      (node (ref "R26") (pin "1") (pinfunction "1_1") (pintype "passive"))
    )
    (net (code "65") (name "Net-(IC5C-O)") (class "Default")
      (node (ref "IC5") (pin "6") (pinfunction "O_6") (pintype "open_collector"))
      (node (ref "R24") (pin "1") (pinfunction "1_1") (pintype "passive"))
    )
    (net (code "66") (name "Net-(IC5D-O)") (class "Default")
      (node (ref "IC5") (pin "8") (pinfunction "O_8") (pintype "open_collector"))
      (node (ref "R28") (pin "1") (pinfunction "1_1") (pintype "passive"))
    )
    (net (code "67") (name "Net-(IC5E-O)") (class "Default")
      (node (ref "IC5") (pin "10") (pinfunction "O_10") (pintype "open_collector"))
      (node (ref "R29") (pin "1") (pinfunction "1_1") (pintype "passive"))
    )
    (net (code "68") (name "Net-(IC5F-O)") (class "Default")
      (node (ref "IC5") (pin "12") (pinfunction "O_12") (pintype "open_collector"))
      (node (ref "R30") (pin "1") (pinfunction "1_1") (pintype "passive"))
    )
    (net (code "69") (name "Net-(IC6A-I1)") (class "Default")
      (node (ref "IC6") (pin "2") (pinfunction "I1_2") (pintype "input"))
      (node (ref "IC6") (pin "6") (pinfunction "O_6") (pintype "output"))
      (node (ref "IC8") (pin "2") (pinfunction "I1_2") (pintype "input"))
    )
    (net (code "70") (name "Net-(IC6A-O)") (class "Default")
      (node (ref "IC6") (pin "3") (pinfunction "O_3") (pintype "output"))
      (node (ref "IC6") (pin "4") (pinfunction "I0_4") (pintype "input"))
    )
    (net (code "71") (name "Net-(IC6C-I1)") (class "Default")
      (node (ref "IC6") (pin "10") (pinfunction "I1_10") (pintype "input"))
      (node (ref "IC6") (pin "11") (pinfunction "O_11") (pintype "output"))
    )
    (net (code "72") (name "Net-(IC6C-O)") (class "Default")
      (node (ref "IC6") (pin "12") (pinfunction "I0_12") (pintype "input"))
      (node (ref "IC6") (pin "8") (pinfunction "O_8") (pintype "output"))
      (node (ref "IC7") (pin "13") (pinfunction "I1_13") (pintype "input"))
    )
    (net (code "73") (name "Net-(IC7A-I0)") (class "Default")
      (node (ref "IC7") (pin "1") (pinfunction "I0_1") (pintype "input"))
      (node (ref "R55") (pin "1") (pinfunction "1_1") (pintype "passive"))
      (node (ref "RUN") (pin "3") (pinfunction "S_3") (pintype "passive"))
    )
    (net (code "74") (name "Net-(IC7A-O)") (class "Default")
      (node (ref "IC7") (pin "3") (pinfunction "O_3") (pintype "output"))
      (node (ref "IC7") (pin "4") (pinfunction "I0_4") (pintype "input"))
    )
    (net (code "75") (name "Net-(IC7B-I1)") (class "Default")
      (node (ref "IC7") (pin "5") (pinfunction "I1_5") (pintype "input"))
      (node (ref "R54") (pin "1") (pinfunction "1_1") (pintype "passive"))
      (node (ref "RUN") (pin "1") (pinfunction "O_1") (pintype "passive"))
    )
    (net (code "76") (name "Net-(IC7C-I0)") (class "Default")
      (node (ref "IC7") (pin "10") (pinfunction "I1_10") (pintype "input"))
      (node (ref "IC7") (pin "11") (pinfunction "O_11") (pintype "output"))
      (node (ref "IC7") (pin "9") (pinfunction "I0_9") (pintype "input"))
    )
    (net (code "77") (name "Net-(IC8B-O)") (class "Default")
      (node (ref "IC8") (pin "6") (pinfunction "O_6") (pintype "output"))
      (node (ref "IC8") (pin "9") (pinfunction "I0_9") (pintype "input"))
    )
    (net (code "78") (name "Net-(IC8C-O)") (class "Default")
      (node (ref "IC8") (pin "12") (pinfunction "I0_12") (pintype "input"))
      (node (ref "IC8") (pin "8") (pinfunction "O_8") (pintype "output"))
    )
    (net (code "79") (name "Net-(IC10A-O)") (class "Default")
      (node (ref "IC10") (pin "2") (pinfunction "O_2") (pintype "open_collector"))
      (node (ref "R31") (pin "1") (pinfunction "1_1") (pintype "passive"))
    )
    (net (code "80") (name "Net-(IC10B-O)") (class "Default")
      (node (ref "IC10") (pin "4") (pinfunction "O_4") (pintype "open_collector"))
      (node (ref "R32") (pin "1") (pinfunction "1_1") (pintype "passive"))
    )
    (net (code "81") (name "Net-(IC10C-O)") (class "Default")
      (node (ref "IC10") (pin "6") (pinfunction "O_6") (pintype "open_collector"))
      (node (ref "R33") (pin "1") (pinfunction "1_1") (pintype "passive"))
    )
    (net (code "82") (name "Net-(IC10D-O)") (class "Default")
      (node (ref "IC10") (pin "8") (pinfunction "O_8") (pintype "open_collector"))
      (node (ref "R36") (pin "1") (pinfunction "1_1") (pintype "passive"))
    )
    (net (code "83") (name "Net-(IC10E-O)") (class "Default")
      (node (ref "IC10") (pin "10") (pinfunction "O_10") (pintype "open_collector"))
      (node (ref "R35") (pin "1") (pinfunction "1_1") (pintype "passive"))
    )
    (net (code "84") (name "Net-(IC10F-O)") (class "Default")
      (node (ref "IC10") (pin "12") (pinfunction "O_12") (pintype "open_collector"))
      (node (ref "R34") (pin "1") (pinfunction "1_1") (pintype "passive"))
    )
    (net (code "85") (name "Net-(IC11A-O)") (class "Default")
      (node (ref "IC11") (pin "2") (pinfunction "O_2") (pintype "open_collector"))
      (node (ref "R37") (pin "1") (pinfunction "1_1") (pintype "passive"))
    )
    (net (code "86") (name "Net-(IC11B-O)") (class "Default")
      (node (ref "IC11") (pin "4") (pinfunction "O_4") (pintype "open_collector"))
      (node (ref "R38") (pin "1") (pinfunction "1_1") (pintype "passive"))
    )
    (net (code "87") (name "Net-(IC11C-O)") (class "Default")
      (node (ref "IC11") (pin "6") (pinfunction "O_6") (pintype "open_collector"))
      (node (ref "R39") (pin "1") (pinfunction "1_1") (pintype "passive"))
    )
    (net (code "88") (name "Net-(IC11D-O)") (class "Default")
      (node (ref "IC11") (pin "8") (pinfunction "O_8") (pintype "open_collector"))
      (node (ref "R40") (pin "1") (pinfunction "1_1") (pintype "passive"))
    )
    (net (code "89") (name "Net-(IC11E-O)") (class "Default")
      (node (ref "IC11") (pin "10") (pinfunction "O_10") (pintype "open_collector"))
      (node (ref "R41") (pin "1") (pinfunction "1_1") (pintype "passive"))
    )
    (net (code "90") (name "Net-(IC11F-O)") (class "Default")
      (node (ref "IC11") (pin "12") (pinfunction "O_12") (pintype "open_collector"))
      (node (ref "R42") (pin "1") (pinfunction "1_1") (pintype "passive"))
    )
    (net (code "91") (name "Net-(IC12A-A)") (class "Default")
      (node (ref "IC12") (pin "5") (pinfunction "A_5") (pintype "input"))
      (node (ref "IC9") (pin "13") (pinfunction "I1_13") (pintype "input"))
      (node (ref "IC9") (pin "3") (pinfunction "O_3") (pintype "output"))
    )
    (net (code "92") (name "Net-(IC12A-C)") (class "Default")
      (node (ref "C1") (pin "1") (pinfunction "1_1") (pintype "passive"))
      (node (ref "IC12") (pin "1") (pinfunction "C_1") (pintype "input"))
    )
    (net (code "93") (name "Net-(IC12A-CLR)") (class "Default")
      (node (ref "IC12") (pin "13") (pinfunction "CLR_13") (pintype "input"))
      (node (ref "IC12") (pin "3") (pinfunction "CLR_3") (pintype "input"))
      (node (ref "R53") (pin "1") (pinfunction "1_1") (pintype "passive"))
    )
    (net (code "94") (name "Net-(IC12A-R{slash}C)") (class "Default")
      (node (ref "C1") (pin "2") (pinfunction "2_2") (pintype "passive"))
      (node (ref "IC12") (pin "2") (pinfunction "R/C_2") (pintype "input"))
      (node (ref "R51") (pin "1") (pinfunction "1_1") (pintype "passive"))
    )
    (net (code "95") (name "Net-(IC12A-~{Q})") (class "Default")
      (node (ref "IC12") (pin "7") (pinfunction "~{Q}_7") (pintype "output"))
      (node (ref "IC9") (pin "10") (pinfunction "I1_10") (pintype "input"))
      (node (ref "IC9") (pin "12") (pinfunction "I0_12") (pintype "input"))
      (node (ref "IC9") (pin "9") (pinfunction "I0_9") (pintype "input"))
    )
    (net (code "96") (name "Net-(IC12B-A)") (class "Default")
      (node (ref "IC12") (pin "11") (pinfunction "A_11") (pintype "input"))
      (node (ref "IC7") (pin "2") (pinfunction "I1_2") (pintype "input"))
      (node (ref "IC7") (pin "6") (pinfunction "O_6") (pintype "output"))
    )
    (net (code "97") (name "Net-(IC12B-B)") (class "Default")
      (node (ref "IC12") (pin "12") (pinfunction "B_12") (pintype "input"))
      (node (ref "IC8") (pin "3") (pinfunction "O_3") (pintype "output"))
      (node (ref "IC8") (pin "4") (pinfunction "I0_4") (pintype "input"))
    )
    (net (code "98") (name "Net-(IC12B-C)") (class "Default")
      (node (ref "C2") (pin "1") (pinfunction "1_1") (pintype "passive"))
      (node (ref "IC12") (pin "15") (pinfunction "C_15") (pintype "input"))
    )
    (net (code "99") (name "Net-(IC12B-Q)") (class "Default")
      (node (ref "IC12") (pin "10") (pinfunction "Q_10") (pintype "output"))
      (node (ref "IC8") (pin "5") (pinfunction "I1_5") (pintype "input"))
    )
    (net (code "100") (name "Net-(IC12B-R{slash}C)") (class "Default")
      (node (ref "C2") (pin "2") (pinfunction "2_2") (pintype "passive"))
      (node (ref "IC12") (pin "14") (pinfunction "R/C_14") (pintype "input"))
      (node (ref "R52") (pin "1") (pinfunction "1_1") (pintype "passive"))
    )
    (net (code "101") (name "Net-(LED1-C)") (class "Default")
      (node (ref "LED1") (pin "K") (pinfunction "C_K") (pintype "passive"))
      (node (ref "R1") (pin "2") (pinfunction "2_2") (pintype "passive"))
    )
    (net (code "102") (name "Net-(LED2-C)") (class "Default")
      (node (ref "LED2") (pin "K") (pinfunction "C_K") (pintype "passive"))
      (node (ref "R2") (pin "2") (pinfunction "2_2") (pintype "passive"))
    )
    (net (code "103") (name "Net-(LED3-C)") (class "Default")
      (node (ref "LED3") (pin "K") (pinfunction "C_K") (pintype "passive"))
      (node (ref "R3") (pin "2") (pinfunction "2_2") (pintype "passive"))
    )
    (net (code "104") (name "Net-(LED4-C)") (class "Default")
      (node (ref "LED4") (pin "K") (pinfunction "C_K") (pintype "passive"))
      (node (ref "R5") (pin "2") (pinfunction "2_2") (pintype "passive"))
    )
    (net (code "105") (name "Net-(LED5-C)") (class "Default")
      (node (ref "LED5") (pin "K") (pinfunction "C_K") (pintype "passive"))
      (node (ref "R4") (pin "2") (pinfunction "2_2") (pintype "passive"))
    )
    (net (code "106") (name "Net-(LED6-C)") (class "Default")
      (node (ref "LED6") (pin "K") (pinfunction "C_K") (pintype "passive"))
      (node (ref "R7") (pin "2") (pinfunction "2_2") (pintype "passive"))
    )
    (net (code "107") (name "Net-(LED7-C)") (class "Default")
      (node (ref "LED7") (pin "K") (pinfunction "C_K") (pintype "passive"))
      (node (ref "R6") (pin "2") (pinfunction "2_2") (pintype "passive"))
    )
    (net (code "108") (name "Net-(LED8-PadA)") (class "Default")
      (node (ref "LED8") (pin "A") (pinfunction "A_A") (pintype "passive"))
      (node (ref "R9") (pin "1") (pinfunction "1_1") (pintype "passive"))
    )
    (net (code "109") (name "Net-(LED9-PadA)") (class "Default")
      (node (ref "LED9") (pin "A") (pinfunction "A_A") (pintype "passive"))
      (node (ref "R8") (pin "1") (pinfunction "1_1") (pintype "passive"))
    )
    (net (code "110") (name "Net-(LED10-C)") (class "Default")
      (node (ref "LED10") (pin "K") (pinfunction "C_K") (pintype "passive"))
      (node (ref "R11") (pin "2") (pinfunction "2_2") (pintype "passive"))
    )
    (net (code "111") (name "Net-(LED11-C)") (class "Default")
      (node (ref "LED11") (pin "K") (pinfunction "C_K") (pintype "passive"))
      (node (ref "R10") (pin "2") (pinfunction "2_2") (pintype "passive"))
    )
    (net (code "112") (name "Net-(LED12-C)") (class "Default")
      (node (ref "LED12") (pin "K") (pinfunction "C_K") (pintype "passive"))
      (node (ref "R13") (pin "2") (pinfunction "2_2") (pintype "passive"))
    )
    (net (code "113") (name "Net-(LED13-C)") (class "Default")
      (node (ref "LED13") (pin "K") (pinfunction "C_K") (pintype "passive"))
      (node (ref "R12") (pin "2") (pinfunction "2_2") (pintype "passive"))
    )
    (net (code "114") (name "Net-(LED14-C)") (class "Default")
      (node (ref "LED14") (pin "K") (pinfunction "C_K") (pintype "passive"))
      (node (ref "R15") (pin "2") (pinfunction "2_2") (pintype "passive"))
    )
    (net (code "115") (name "Net-(LED15-C)") (class "Default")
      (node (ref "LED15") (pin "K") (pinfunction "C_K") (pintype "passive"))
      (node (ref "R14") (pin "2") (pinfunction "2_2") (pintype "passive"))
    )
    (net (code "116") (name "Net-(LED16-C)") (class "Default")
      (node (ref "LED16") (pin "K") (pinfunction "C_K") (pintype "passive"))
      (node (ref "R16") (pin "2") (pinfunction "2_2") (pintype "passive"))
    )
    (net (code "117") (name "Net-(LED17-C)") (class "Default")
      (node (ref "LED17") (pin "K") (pinfunction "C_K") (pintype "passive"))
      (node (ref "R17") (pin "2") (pinfunction "2_2") (pintype "passive"))
    )
    (net (code "118") (name "Net-(LED18-C)") (class "Default")
      (node (ref "LED18") (pin "K") (pinfunction "C_K") (pintype "passive"))
      (node (ref "R18") (pin "2") (pinfunction "2_2") (pintype "passive"))
    )
    (net (code "119") (name "Net-(LED19-C)") (class "Default")
      (node (ref "LED19") (pin "K") (pinfunction "C_K") (pintype "passive"))
      (node (ref "R19") (pin "2") (pinfunction "2_2") (pintype "passive"))
    )
    (net (code "120") (name "Net-(LED20-C)") (class "Default")
      (node (ref "LED20") (pin "K") (pinfunction "C_K") (pintype "passive"))
      (node (ref "R20") (pin "2") (pinfunction "2_2") (pintype "passive"))
    )
    (net (code "121") (name "Net-(LED21-C)") (class "Default")
      (node (ref "LED21") (pin "K") (pinfunction "C_K") (pintype "passive"))
      (node (ref "R21") (pin "2") (pinfunction "2_2") (pintype "passive"))
    )
    (net (code "122") (name "Net-(LED22-C)") (class "Default")
      (node (ref "LED22") (pin "K") (pinfunction "C_K") (pintype "passive"))
      (node (ref "R23") (pin "2") (pinfunction "2_2") (pintype "passive"))
    )
    (net (code "123") (name "Net-(LED23-C)") (class "Default")
      (node (ref "LED23") (pin "K") (pinfunction "C_K") (pintype "passive"))
      (node (ref "R22") (pin "2") (pinfunction "2_2") (pintype "passive"))
    )
    (net (code "124") (name "Net-(LED24-C)") (class "Default")
      (node (ref "LED24") (pin "K") (pinfunction "C_K") (pintype "passive"))
      (node (ref "R25") (pin "2") (pinfunction "2_2") (pintype "passive"))
    )
    (net (code "125") (name "Net-(LED25-C)") (class "Default")
      (node (ref "LED25") (pin "K") (pinfunction "C_K") (pintype "passive"))
      (node (ref "R24") (pin "2") (pinfunction "2_2") (pintype "passive"))
    )
    (net (code "126") (name "Net-(LED26-C)") (class "Default")
      (node (ref "LED26") (pin "K") (pinfunction "C_K") (pintype "passive"))
      (node (ref "R27") (pin "2") (pinfunction "2_2") (pintype "passive"))
    )
    (net (code "127") (name "Net-(LED27-C)") (class "Default")
      (node (ref "LED27") (pin "K") (pinfunction "C_K") (pintype "passive"))
      (node (ref "R26") (pin "2") (pinfunction "2_2") (pintype "passive"))
    )
    (net (code "128") (name "Net-(LED28-C)") (class "Default")
      (node (ref "LED28") (pin "K") (pinfunction "C_K") (pintype "passive"))
      (node (ref "R28") (pin "2") (pinfunction "2_2") (pintype "passive"))
    )
    (net (code "129") (name "Net-(LED29-C)") (class "Default")
      (node (ref "LED29") (pin "K") (pinfunction "C_K") (pintype "passive"))
      (node (ref "R29") (pin "2") (pinfunction "2_2") (pintype "passive"))
    )
    (net (code "130") (name "Net-(LED30-C)") (class "Default")
      (node (ref "LED30") (pin "K") (pinfunction "C_K") (pintype "passive"))
      (node (ref "R30") (pin "2") (pinfunction "2_2") (pintype "passive"))
    )
    (net (code "131") (name "Net-(LED31-C)") (class "Default")
      (node (ref "LED31") (pin "K") (pinfunction "C_K") (pintype "passive"))
      (node (ref "R32") (pin "2") (pinfunction "2_2") (pintype "passive"))
    )
    (net (code "132") (name "Net-(LED32-C)") (class "Default")
      (node (ref "LED32") (pin "K") (pinfunction "C_K") (pintype "passive"))
      (node (ref "R31") (pin "2") (pinfunction "2_2") (pintype "passive"))
    )
    (net (code "133") (name "Net-(LED33-C)") (class "Default")
      (node (ref "LED33") (pin "K") (pinfunction "C_K") (pintype "passive"))
      (node (ref "R33") (pin "2") (pinfunction "2_2") (pintype "passive"))
    )
    (net (code "134") (name "Net-(LED34-C)") (class "Default")
      (node (ref "LED34") (pin "K") (pinfunction "C_K") (pintype "passive"))
      (node (ref "R34") (pin "2") (pinfunction "2_2") (pintype "passive"))
    )
    (net (code "135") (name "Net-(LED35-C)") (class "Default")
      (node (ref "LED35") (pin "K") (pinfunction "C_K") (pintype "passive"))
      (node (ref "R35") (pin "2") (pinfunction "2_2") (pintype "passive"))
    )
    (net (code "136") (name "Net-(LED36-C)") (class "Default")
      (node (ref "LED36") (pin "K") (pinfunction "C_K") (pintype "passive"))
      (node (ref "R36") (pin "2") (pinfunction "2_2") (pintype "passive"))
    )
    (net (code "137") (name "Net-(LED37-C)") (class "Default")
      (node (ref "LED37") (pin "K") (pinfunction "C_K") (pintype "passive"))
      (node (ref "R37") (pin "2") (pinfunction "2_2") (pintype "passive"))
    )
    (net (code "138") (name "Net-(LED38-C)") (class "Default")
      (node (ref "LED38") (pin "K") (pinfunction "C_K") (pintype "passive"))
      (node (ref "R38") (pin "2") (pinfunction "2_2") (pintype "passive"))
    )
    (net (code "139") (name "Net-(LED39-C)") (class "Default")
      (node (ref "LED39") (pin "K") (pinfunction "C_K") (pintype "passive"))
      (node (ref "R39") (pin "2") (pinfunction "2_2") (pintype "passive"))
    )
    (net (code "140") (name "Net-(LED40-C)") (class "Default")
      (node (ref "LED40") (pin "K") (pinfunction "C_K") (pintype "passive"))
      (node (ref "R40") (pin "2") (pinfunction "2_2") (pintype "passive"))
    )
    (net (code "141") (name "Net-(LED41-C)") (class "Default")
      (node (ref "LED41") (pin "K") (pinfunction "C_K") (pintype "passive"))
      (node (ref "R41") (pin "2") (pinfunction "2_2") (pintype "passive"))
    )
    (net (code "142") (name "Net-(LED42-C)") (class "Default")
      (node (ref "LED42") (pin "K") (pinfunction "C_K") (pintype "passive"))
      (node (ref "R42") (pin "2") (pinfunction "2_2") (pintype "passive"))
    )
    (net (code "143") (name "Net-(SLOW-O)") (class "Default")
      (node (ref "C4") (pin "-") (pinfunction "-_-") (pintype "passive"))
      (node (ref "SLOW") (pin "1") (pinfunction "O_1") (pintype "passive"))
      (node (ref "SLOW") (pin "2") (pinfunction "P_2") (pintype "passive"))
    )
    (net (code "144") (name "Net-(SW0-O)") (class "Default")
      (node (ref "R50") (pin "1") (pinfunction "1_1") (pintype "passive"))
      (node (ref "SR0") (pin "1") (pinfunction "1_1") (pintype "passive"))
      (node (ref "SW0") (pin "1") (pinfunction "O_1") (pintype "passive"))
      (node (ref "SW0") (pin "2") (pinfunction "P_2") (pintype "passive"))
    )
    (net (code "145") (name "Net-(SW1-O)") (class "Default")
      (node (ref "R49") (pin "1") (pinfunction "1_1") (pintype "passive"))
      (node (ref "SR1") (pin "1") (pinfunction "1_1") (pintype "passive"))
      (node (ref "SW1") (pin "1") (pinfunction "O_1") (pintype "passive"))
      (node (ref "SW1") (pin "2") (pinfunction "P_2") (pintype "passive"))
    )
    (net (code "146") (name "Net-(SW2-O)") (class "Default")
      (node (ref "R48") (pin "1") (pinfunction "1_1") (pintype "passive"))
      (node (ref "SR2") (pin "1") (pinfunction "1_1") (pintype "passive"))
      (node (ref "SW2") (pin "1") (pinfunction "O_1") (pintype "passive"))
      (node (ref "SW2") (pin "2") (pinfunction "P_2") (pintype "passive"))
    )
    (net (code "147") (name "Net-(SW3-O)") (class "Default")
      (node (ref "R47") (pin "1") (pinfunction "1_1") (pintype "passive"))
      (node (ref "SR3") (pin "1") (pinfunction "1_1") (pintype "passive"))
      (node (ref "SW3") (pin "1") (pinfunction "O_1") (pintype "passive"))
      (node (ref "SW3") (pin "2") (pinfunction "P_2") (pintype "passive"))
    )
    (net (code "148") (name "Net-(SW4-O)") (class "Default")
      (node (ref "R46") (pin "1") (pinfunction "1_1") (pintype "passive"))
      (node (ref "SR4") (pin "1") (pinfunction "1_1") (pintype "passive"))
      (node (ref "SW4") (pin "1") (pinfunction "O_1") (pintype "passive"))
      (node (ref "SW4") (pin "2") (pinfunction "P_2") (pintype "passive"))
    )
    (net (code "149") (name "Net-(SW5-O)") (class "Default")
      (node (ref "R45") (pin "1") (pinfunction "1_1") (pintype "passive"))
      (node (ref "SR5") (pin "1") (pinfunction "1_1") (pintype "passive"))
      (node (ref "SW5") (pin "1") (pinfunction "O_1") (pintype "passive"))
      (node (ref "SW5") (pin "2") (pinfunction "P_2") (pintype "passive"))
    )
    (net (code "150") (name "Net-(SW6-O)") (class "Default")
      (node (ref "R44") (pin "1") (pinfunction "1_1") (pintype "passive"))
      (node (ref "SR6") (pin "1") (pinfunction "1_1") (pintype "passive"))
      (node (ref "SW6") (pin "1") (pinfunction "O_1") (pintype "passive"))
      (node (ref "SW6") (pin "2") (pinfunction "P_2") (pintype "passive"))
    )
    (net (code "151") (name "Net-(SW7-O)") (class "Default")
      (node (ref "R43") (pin "1") (pinfunction "1_1") (pintype "passive"))
      (node (ref "SR7") (pin "1") (pinfunction "1_1") (pintype "passive"))
      (node (ref "SW7") (pin "1") (pinfunction "O_1") (pintype "passive"))
      (node (ref "SW7") (pin "2") (pinfunction "P_2") (pintype "passive"))
    )
    (net (code "152") (name "OPR") (class "Default")
      (node (ref "IC10") (pin "1") (pinfunction "I_1") (pintype "input"))
      (node (ref "OPR") (pin "1") (pinfunction "1_1") (pintype "passive"))
    )
    (net (code "153") (name "PC0") (class "Default")
      (node (ref "IC5") (pin "11") (pinfunction "I_11") (pintype "input"))
      (node (ref "PC0") (pin "1") (pinfunction "1_1") (pintype "passive"))
    )
    (net (code "154") (name "PC1") (class "Default")
      (node (ref "IC5") (pin "1") (pinfunction "I_1") (pintype "input"))
      (node (ref "PC1") (pin "1") (pinfunction "1_1") (pintype "passive"))
    )
    (net (code "155") (name "PC2") (class "Default")
      (node (ref "IC5") (pin "5") (pinfunction "I_5") (pintype "input"))
      (node (ref "PC2") (pin "1") (pinfunction "1_1") (pintype "passive"))
    )
    (net (code "156") (name "PC3") (class "Default")
      (node (ref "IC4") (pin "11") (pinfunction "I_11") (pintype "input"))
      (node (ref "PC3") (pin "1") (pinfunction "1_1") (pintype "passive"))
    )
    (net (code "157") (name "PC4") (class "Default")
      (node (ref "IC4") (pin "5") (pinfunction "I_5") (pintype "input"))
      (node (ref "PC4") (pin "1") (pinfunction "1_1") (pintype "passive"))
    )
    (net (code "158") (name "PC5") (class "Default")
      (node (ref "IC2") (pin "11") (pinfunction "I_11") (pintype "input"))
      (node (ref "PC5") (pin "1") (pinfunction "1_1") (pintype "passive"))
    )
    (net (code "159") (name "PC6") (class "Default")
      (node (ref "IC2") (pin "13") (pinfunction "I_13") (pintype "input"))
      (node (ref "PC6") (pin "1") (pinfunction "1_1") (pintype "passive"))
    )
    (net (code "160") (name "TAD") (class "Default")
      (node (ref "IC11") (pin "1") (pinfunction "I_1") (pintype "input"))
      (node (ref "TAD") (pin "1") (pinfunction "1_1") (pintype "passive"))
    )
    (net (code "161") (name "VCC") (class "Default")
      (node (ref "C6") (pin "1") (pinfunction "1_1") (pintype "passive"))
      (node (ref "C7") (pin "1") (pinfunction "1_1") (pintype "passive"))
      (node (ref "LED1") (pin "A") (pinfunction "A_A") (pintype "passive"))
      (node (ref "LED10") (pin "A") (pinfunction "A_A") (pintype "passive"))
      (node (ref "LED11") (pin "A") (pinfunction "A_A") (pintype "passive"))
      (node (ref "LED12") (pin "A") (pinfunction "A_A") (pintype "passive"))
      (node (ref "LED13") (pin "A") (pinfunction "A_A") (pintype "passive"))
      (node (ref "LED14") (pin "A") (pinfunction "A_A") (pintype "passive"))
      (node (ref "LED15") (pin "A") (pinfunction "A_A") (pintype "passive"))
      (node (ref "LED16") (pin "A") (pinfunction "A_A") (pintype "passive"))
      (node (ref "LED17") (pin "A") (pinfunction "A_A") (pintype "passive"))
      (node (ref "LED18") (pin "A") (pinfunction "A_A") (pintype "passive"))
      (node (ref "LED19") (pin "A") (pinfunction "A_A") (pintype "passive"))
      (node (ref "LED2") (pin "A") (pinfunction "A_A") (pintype "passive"))
      (node (ref "LED20") (pin "A") (pinfunction "A_A") (pintype "passive"))
      (node (ref "LED21") (pin "A") (pinfunction "A_A") (pintype "passive"))
      (node (ref "LED22") (pin "A") (pinfunction "A_A") (pintype "passive"))
      (node (ref "LED23") (pin "A") (pinfunction "A_A") (pintype "passive"))
      (node (ref "LED24") (pin "A") (pinfunction "A_A") (pintype "passive"))
      (node (ref "LED25") (pin "A") (pinfunction "A_A") (pintype "passive"))
      (node (ref "LED26") (pin "A") (pinfunction "A_A") (pintype "passive"))
      (node (ref "LED27") (pin "A") (pinfunction "A_A") (pintype "passive"))
      (node (ref "LED28") (pin "A") (pinfunction "A_A") (pintype "passive"))
      (node (ref "LED29") (pin "A") (pinfunction "A_A") (pintype "passive"))
      (node (ref "LED3") (pin "A") (pinfunction "A_A") (pintype "passive"))
      (node (ref "LED30") (pin "A") (pinfunction "A_A") (pintype "passive"))
      (node (ref "LED31") (pin "A") (pinfunction "A_A") (pintype "passive"))
      (node (ref "LED32") (pin "A") (pinfunction "A_A") (pintype "passive"))
      (node (ref "LED33") (pin "A") (pinfunction "A_A") (pintype "passive"))
      (node (ref "LED34") (pin "A") (pinfunction "A_A") (pintype "passive"))
      (node (ref "LED35") (pin "A") (pinfunction "A_A") (pintype "passive"))
      (node (ref "LED36") (pin "A") (pinfunction "A_A") (pintype "passive"))
      (node (ref "LED37") (pin "A") (pinfunction "A_A") (pintype "passive"))
      (node (ref "LED38") (pin "A") (pinfunction "A_A") (pintype "passive"))
      (node (ref "LED39") (pin "A") (pinfunction "A_A") (pintype "passive"))
      (node (ref "LED4") (pin "A") (pinfunction "A_A") (pintype "passive"))
      (node (ref "LED40") (pin "A") (pinfunction "A_A") (pintype "passive"))
      (node (ref "LED41") (pin "A") (pinfunction "A_A") (pintype "passive"))
      (node (ref "LED42") (pin "A") (pinfunction "A_A") (pintype "passive"))
      (node (ref "LED5") (pin "A") (pinfunction "A_A") (pintype "passive"))
      (node (ref "LED6") (pin "A") (pinfunction "A_A") (pintype "passive"))
      (node (ref "LED7") (pin "A") (pinfunction "A_A") (pintype "passive"))
      (node (ref "R43") (pin "2") (pinfunction "2_2") (pintype "passive"))
      (node (ref "R44") (pin "2") (pinfunction "2_2") (pintype "passive"))
      (node (ref "R45") (pin "2") (pinfunction "2_2") (pintype "passive"))
      (node (ref "R46") (pin "2") (pinfunction "2_2") (pintype "passive"))
      (node (ref "R47") (pin "2") (pinfunction "2_2") (pintype "passive"))
      (node (ref "R48") (pin "2") (pinfunction "2_2") (pintype "passive"))
      (node (ref "R49") (pin "2") (pinfunction "2_2") (pintype "passive"))
      (node (ref "R50") (pin "2") (pinfunction "2_2") (pintype "passive"))
      (node (ref "R51") (pin "2") (pinfunction "2_2") (pintype "passive"))
      (node (ref "R52") (pin "2") (pinfunction "2_2") (pintype "passive"))
      (node (ref "R53") (pin "2") (pinfunction "2_2") (pintype "passive"))
      (node (ref "R54") (pin "2") (pinfunction "2_2") (pintype "passive"))
      (node (ref "R55") (pin "2") (pinfunction "2_2") (pintype "passive"))
      (node (ref "R56") (pin "2") (pinfunction "2_2") (pintype "passive"))
      (node (ref "R57") (pin "2") (pinfunction "2_2") (pintype "passive"))
      (node (ref "R58") (pin "2") (pinfunction "2_2") (pintype "passive"))
      (node (ref "R59") (pin "2") (pinfunction "2_2") (pintype "passive"))
      (node (ref "R60") (pin "2") (pinfunction "2_2") (pintype "passive"))
      (node (ref "R61") (pin "2") (pinfunction "2_2") (pintype "passive"))
      (node (ref "R62") (pin "2") (pinfunction "2_2") (pintype "passive"))
      (node (ref "R8") (pin "2") (pinfunction "2_2") (pintype "passive"))
      (node (ref "R9") (pin "2") (pinfunction "2_2") (pintype "passive"))
      (node (ref "VCC") (pin "1") (pinfunction "1_1") (pintype "passive"))
    )
    (net (code "162") (name "unconnected-(IC12A-Q-Pad6)") (class "Default")
      (node (ref "IC12") (pin "6") (pinfunction "Q_6") (pintype "output"))
    )
    (net (code "163") (name "~{CNCL_DEP_EX}") (class "Default")
      (node (ref "!CNCL_DEP_EX") (pin "1") (pinfunction "1_1") (pintype "passive"))
      (node (ref "IC8") (pin "13") (pinfunction "I1_13") (pintype "input"))
    )
    (net (code "164") (name "~{DEFER}") (class "Default")
      (node (ref "!DEFER") (pin "1") (pinfunction "1_1") (pintype "passive"))
      (node (ref "IC11") (pin "13") (pinfunction "I_13") (pintype "input"))
    )
    (net (code "165") (name "~{DEPOSIT}") (class "Default")
      (node (ref "!DEPOSIT") (pin "1") (pinfunction "1_1") (pintype "passive"))
      (node (ref "IC7") (pin "8") (pinfunction "O_8") (pintype "output"))
      (node (ref "IC8") (pin "1") (pinfunction "I0_1") (pintype "input"))
    )
    (net (code "166") (name "~{DEP_EX}") (class "Default")
      (node (ref "!DEP_EX") (pin "1") (pinfunction "1_1") (pintype "passive"))
      (node (ref "IC8") (pin "10") (pinfunction "I1_10") (pintype "input"))
      (node (ref "IC8") (pin "11") (pinfunction "O_11") (pintype "output"))
    )
    (net (code "167") (name "~{EXEC}") (class "Default")
      (node (ref "!EXEC") (pin "1") (pinfunction "1_1") (pintype "passive"))
      (node (ref "IC11") (pin "5") (pinfunction "I_5") (pintype "input"))
    )
    (net (code "168") (name "~{EXT_DEP}") (class "Default")
      (node (ref "!EXT_DEP") (pin "1") (pinfunction "1_1") (pintype "passive"))
      (node (ref "C3") (pin "1") (pinfunction "1_1") (pintype "passive"))
      (node (ref "IC7") (pin "12") (pinfunction "I0_12") (pintype "input"))
      (node (ref "R56") (pin "1") (pinfunction "1_1") (pintype "passive"))
    )
    (net (code "169") (name "~{EXT_LA}") (class "Default")
      (node (ref "!EXT_LA") (pin "1") (pinfunction "1_1") (pintype "passive"))
      (node (ref "C5") (pin "1") (pinfunction "1_1") (pintype "passive"))
      (node (ref "IC9") (pin "1") (pinfunction "I0_1") (pintype "input"))
      (node (ref "IC9") (pin "2") (pinfunction "I1_2") (pintype "input"))
      (node (ref "LA") (pin "1") (pinfunction "O_1") (pintype "passive"))
      (node (ref "R62") (pin "1") (pinfunction "1_1") (pintype "passive"))
    )
    (net (code "170") (name "~{FETCH}") (class "Default")
      (node (ref "!FETCH") (pin "1") (pinfunction "1_1") (pintype "passive"))
      (node (ref "IC11") (pin "11") (pinfunction "I_11") (pintype "input"))
    )
    (net (code "171") (name "~{HLT}") (class "Default")
      (node (ref "!HLT") (pin "1") (pinfunction "1_1") (pintype "passive"))
      (node (ref "IC9") (pin "5") (pinfunction "I1_5") (pintype "input"))
    )
    (net (code "172") (name "~{LA1}") (class "Default")
      (node (ref "!LA1") (pin "1") (pinfunction "1_1") (pintype "passive"))
      (node (ref "IC9") (pin "11") (pinfunction "O_11") (pintype "output"))
    )
    (net (code "173") (name "~{RUN_CMD}") (class "Default")
      (node (ref "!RUN_CMD") (pin "1") (pinfunction "1_1") (pintype "passive"))
      (node (ref "IC12") (pin "9") (pinfunction "~{Q}_9") (pintype "output"))
    )
    (net (code "174") (name "~{RUN}") (class "Default")
      (node (ref "!RUN") (pin "1") (pinfunction "1_1") (pintype "passive"))
      (node (ref "IC11") (pin "9") (pinfunction "I_9") (pintype "input"))
    )
  )
)
